# VCFA_bjt.net
KiCad netlist of a schematic drawn in EAGLE
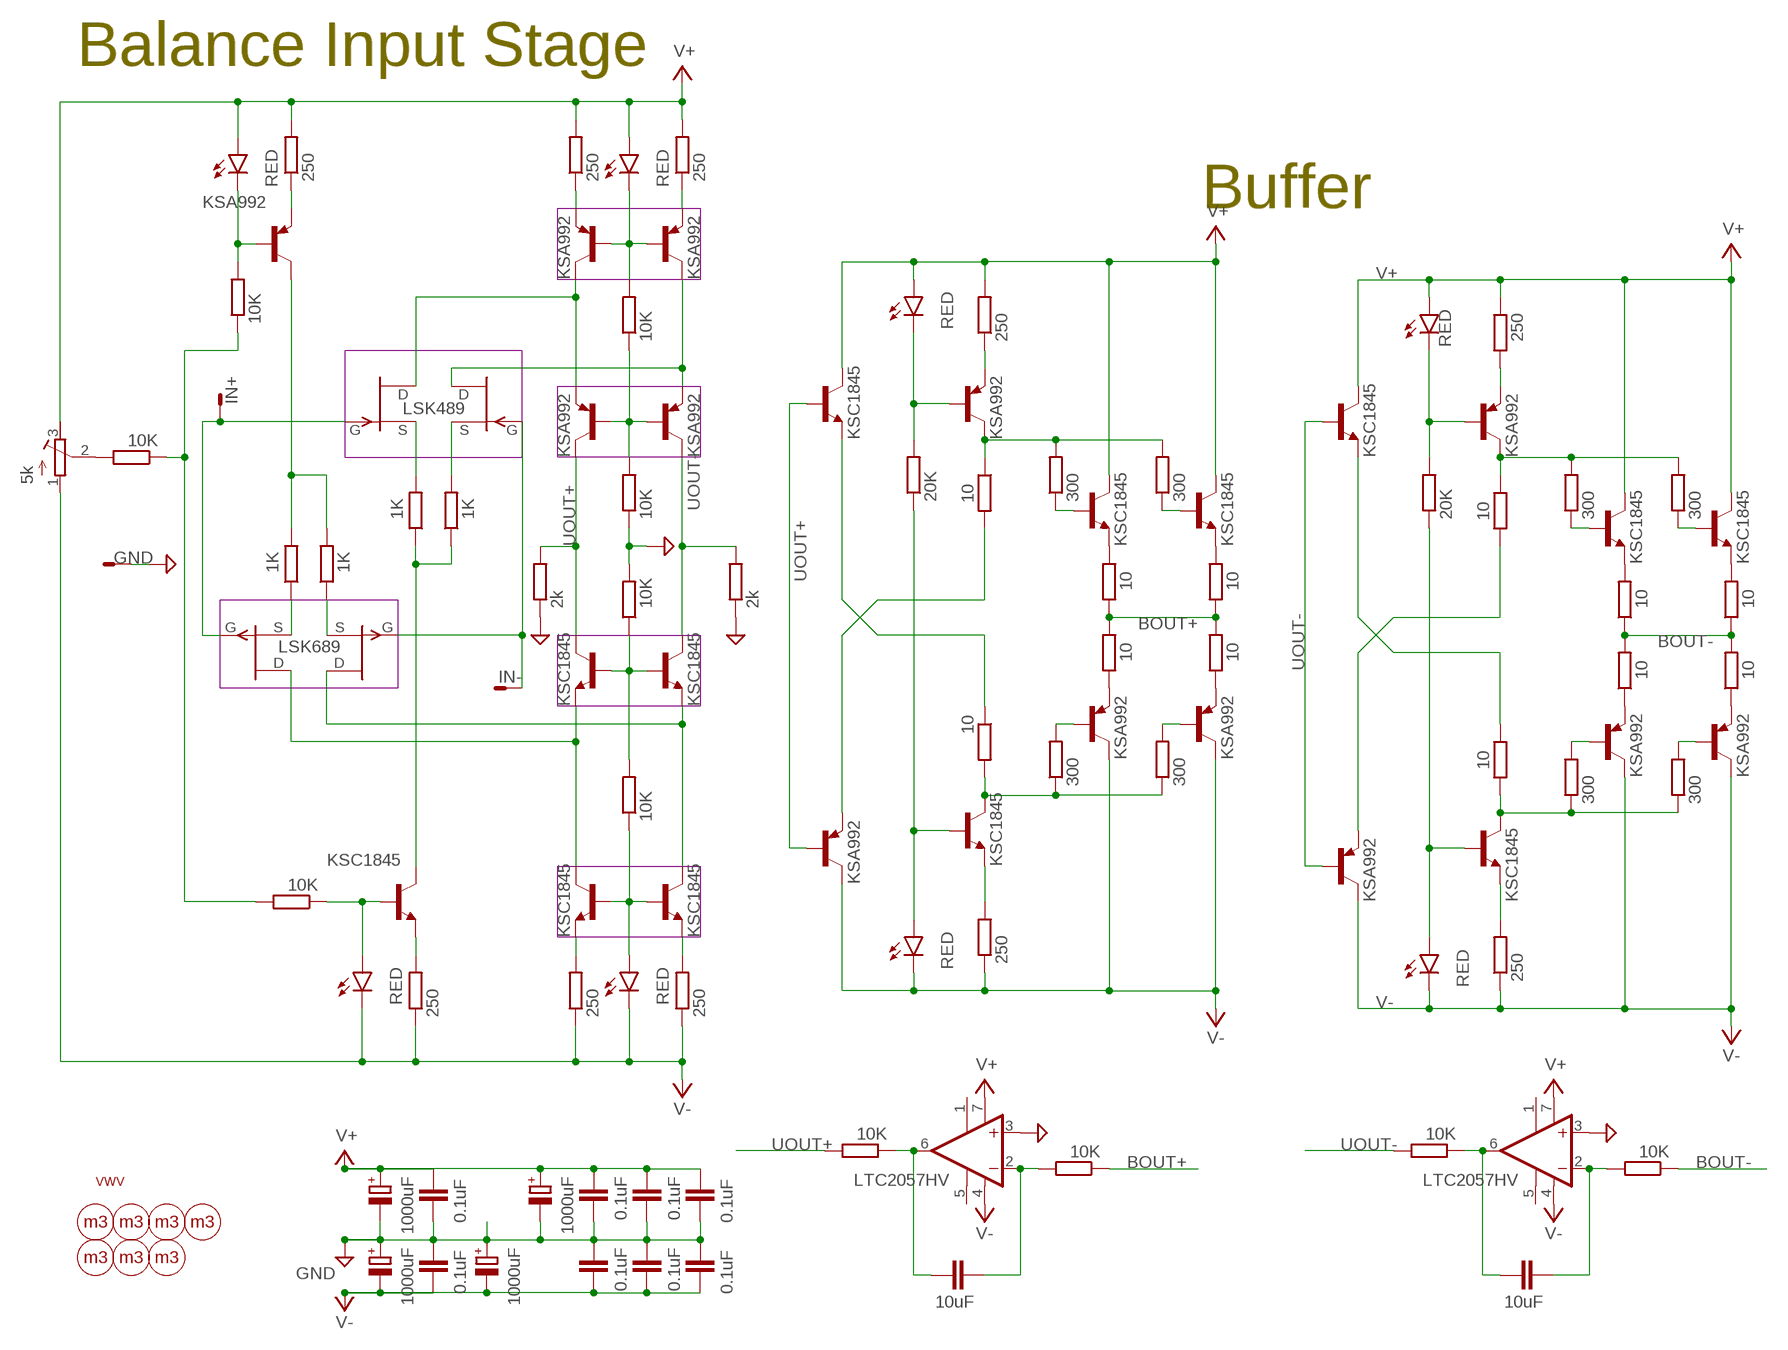
[diagram p0: schematic, sheet 1]
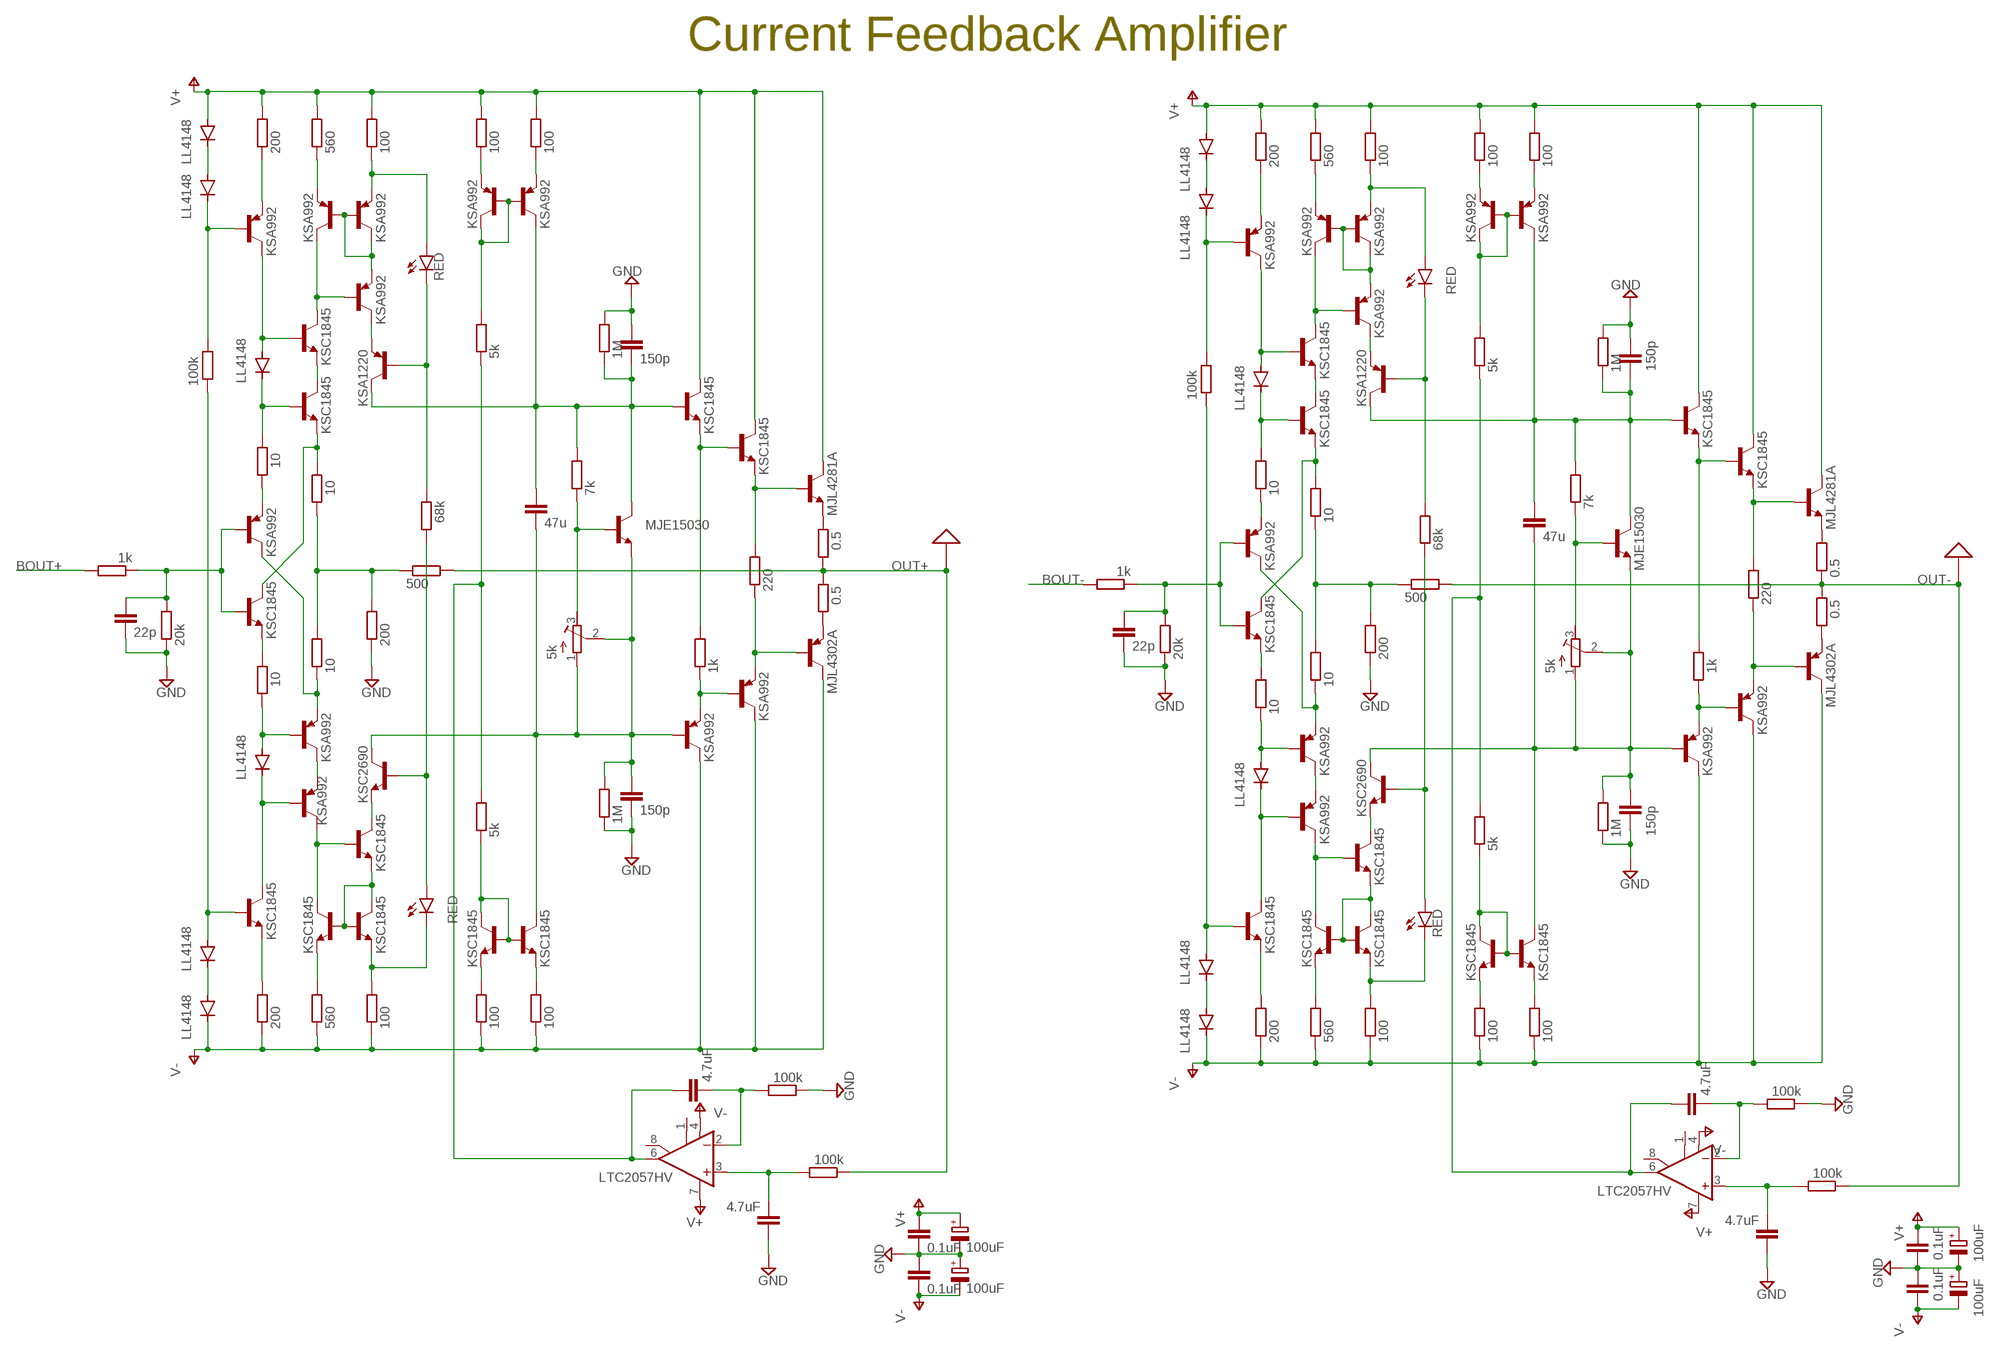
[diagram p1: schematic, sheet 2]
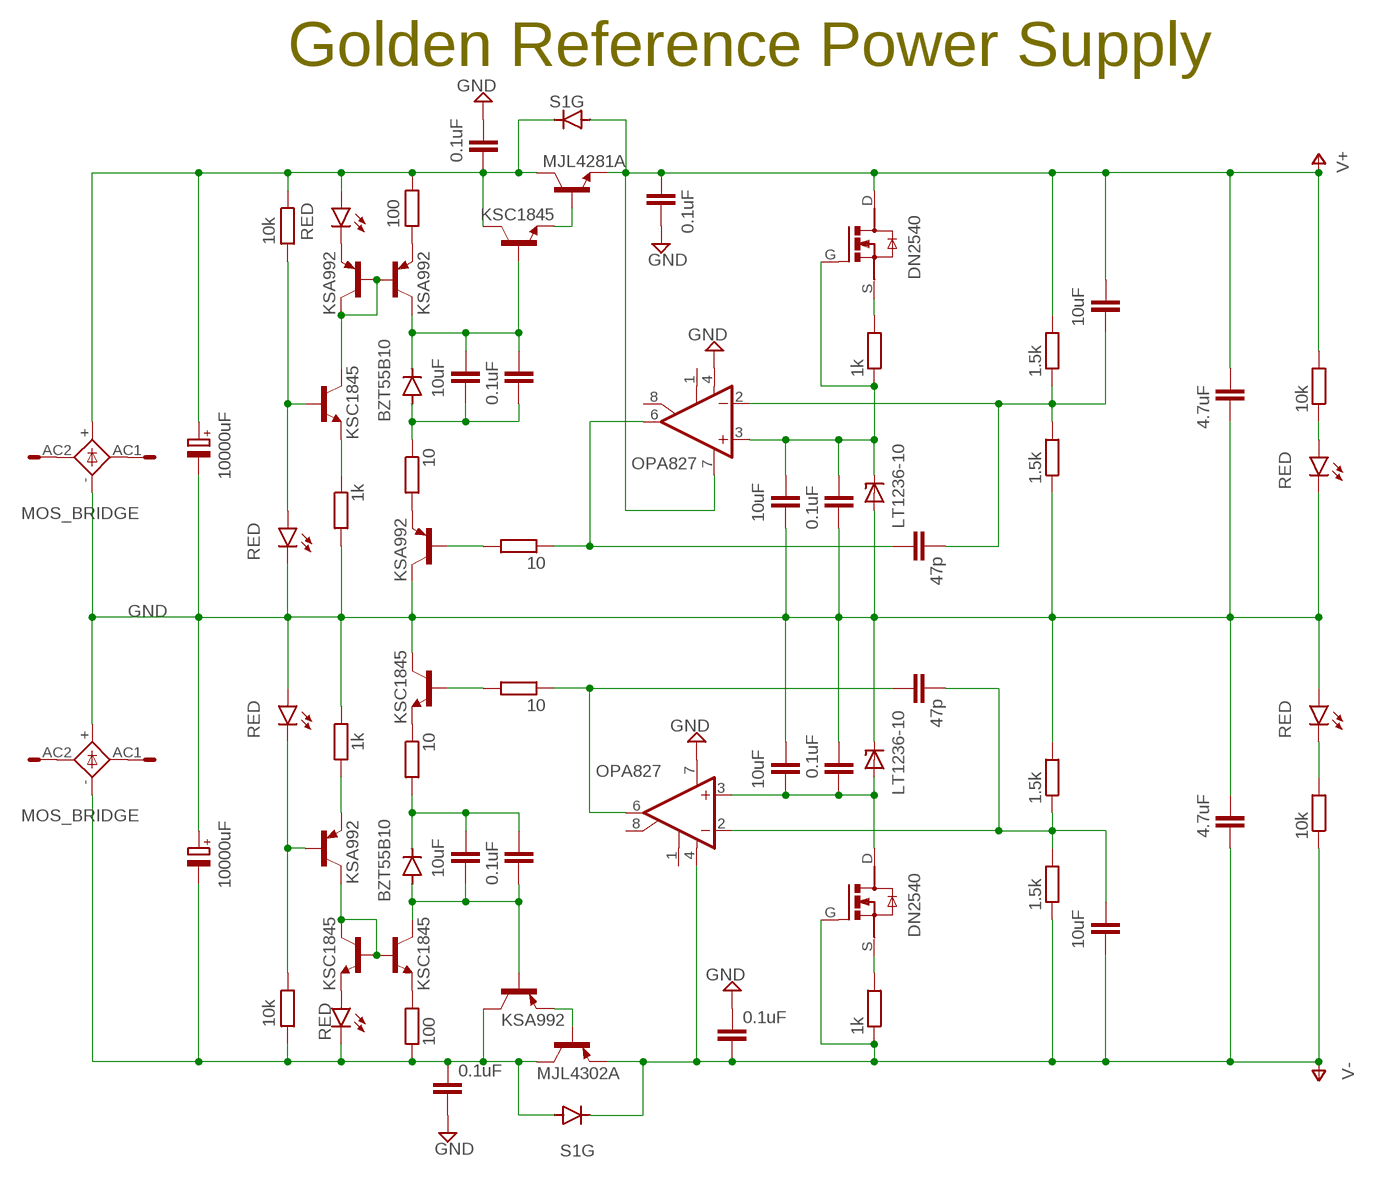
[diagram p2: schematic, sheet 3]

(export (version "E")
  (design (tool "Eeschema 10.0.6"))
  (components
    (comp (ref "C17")
      (value "22p")
      (footprint "eagle-import:C0805")
      (fields (field (name "SPICEPREFIX") "C"))
      (libsource (lib "eagle-import") (part "C-EUC0805"))
    )
    (comp (ref "C18")
      (value "47u")
      (footprint "eagle-import:C1210")
      (fields (field (name "SPICEPREFIX") "C"))
      (libsource (lib "eagle-import") (part "C-EUC1210"))
    )
    (comp (ref "C19")
      (value "150p")
      (footprint "eagle-import:C0805")
      (fields (field (name "SPICEPREFIX") "C"))
      (libsource (lib "eagle-import") (part "C-EUC0805"))
    )
    (comp (ref "C20")
      (value "150p")
      (footprint "eagle-import:C0805")
      (fields (field (name "SPICEPREFIX") "C"))
      (libsource (lib "eagle-import") (part "C-EUC0805"))
    )
    (comp (ref "C21")
      (value "4.7uF")
      (footprint "eagle-import:C1210")
      (fields (field (name "SPICEPREFIX") "C"))
      (libsource (lib "eagle-import") (part "C-EUC1210"))
    )
    (comp (ref "C22")
      (value "4.7uF")
      (footprint "eagle-import:C1210")
      (fields (field (name "SPICEPREFIX") "C"))
      (libsource (lib "eagle-import") (part "C-EUC1210"))
    )
    (comp (ref "C23")
      (value "0.1uF")
      (footprint "eagle-import:C0603K")
      (libsource (lib "eagle-import") (part "C-EUC0603K"))
    )
    (comp (ref "C24")
      (value "0.1uF")
      (footprint "eagle-import:C0603K")
      (libsource (lib "eagle-import") (part "C-EUC0603K"))
    )
    (comp (ref "C25")
      (value "100uF")
      (footprint "eagle-import:E3,5-8")
      (libsource (lib "eagle-import") (part "CPOL-EUE3.5-8"))
    )
    (comp (ref "C26")
      (value "100uF")
      (footprint "eagle-import:E3,5-8")
      (libsource (lib "eagle-import") (part "CPOL-EUE3.5-8"))
    )
    (comp (ref "C27")
      (value "22p")
      (footprint "eagle-import:C0805")
      (fields (field (name "SPICEPREFIX") "C"))
      (libsource (lib "eagle-import") (part "C-EUC0805"))
    )
    (comp (ref "C28")
      (value "47u")
      (footprint "eagle-import:C1210")
      (fields (field (name "SPICEPREFIX") "C"))
      (libsource (lib "eagle-import") (part "C-EUC1210"))
    )
    (comp (ref "C29")
      (value "150p")
      (footprint "eagle-import:C0805")
      (fields (field (name "SPICEPREFIX") "C"))
      (libsource (lib "eagle-import") (part "C-EUC0805"))
    )
    (comp (ref "C30")
      (value "150p")
      (footprint "eagle-import:C0805")
      (fields (field (name "SPICEPREFIX") "C"))
      (libsource (lib "eagle-import") (part "C-EUC0805"))
    )
    (comp (ref "C31")
      (value "4.7uF")
      (footprint "eagle-import:C1210")
      (fields (field (name "SPICEPREFIX") "C"))
      (libsource (lib "eagle-import") (part "C-EUC1210"))
    )
    (comp (ref "C32")
      (value "4.7uF")
      (footprint "eagle-import:C1210")
      (fields (field (name "SPICEPREFIX") "C"))
      (libsource (lib "eagle-import") (part "C-EUC1210"))
    )
    (comp (ref "C33")
      (value "0.1uF")
      (footprint "eagle-import:C0603K")
      (libsource (lib "eagle-import") (part "C-EUC0603K"))
    )
    (comp (ref "C34")
      (value "0.1uF")
      (footprint "eagle-import:C0603K")
      (libsource (lib "eagle-import") (part "C-EUC0603K"))
    )
    (comp (ref "C35")
      (value "100uF")
      (footprint "eagle-import:E3,5-8")
      (libsource (lib "eagle-import") (part "CPOL-EUE3.5-8"))
    )
    (comp (ref "C36")
      (value "100uF")
      (footprint "eagle-import:E3,5-8")
      (libsource (lib "eagle-import") (part "CPOL-EUE3.5-8"))
    )
    (comp (ref "D1")
      (value "LL4148")
      (footprint "eagle-import:SOD80C")
      (fields (field (name "SPICEPREFIX") "D"))
      (libsource (lib "eagle-import") (part "DIODE-SOD80C"))
    )
    (comp (ref "D2")
      (value "LL4148")
      (footprint "eagle-import:SOD80C")
      (fields (field (name "SPICEPREFIX") "D"))
      (libsource (lib "eagle-import") (part "DIODE-SOD80C"))
    )
    (comp (ref "D3")
      (value "LL4148")
      (footprint "eagle-import:SOD80C")
      (fields (field (name "SPICEPREFIX") "D"))
      (libsource (lib "eagle-import") (part "DIODE-SOD80C"))
    )
    (comp (ref "D4")
      (value "LL4148")
      (footprint "eagle-import:SOD80C")
      (fields (field (name "SPICEPREFIX") "D"))
      (libsource (lib "eagle-import") (part "DIODE-SOD80C"))
    )
    (comp (ref "D5")
      (value "LL4148")
      (footprint "eagle-import:SOD80C")
      (fields (field (name "SPICEPREFIX") "D"))
      (libsource (lib "eagle-import") (part "DIODE-SOD80C"))
    )
    (comp (ref "D6")
      (value "LL4148")
      (footprint "eagle-import:SOD80C")
      (fields (field (name "SPICEPREFIX") "D"))
      (libsource (lib "eagle-import") (part "DIODE-SOD80C"))
    )
    (comp (ref "D7")
      (value "LL4148")
      (footprint "eagle-import:SOD80C")
      (fields (field (name "SPICEPREFIX") "D"))
      (libsource (lib "eagle-import") (part "DIODE-SOD80C"))
    )
    (comp (ref "D8")
      (value "LL4148")
      (footprint "eagle-import:SOD80C")
      (fields (field (name "SPICEPREFIX") "D"))
      (libsource (lib "eagle-import") (part "DIODE-SOD80C"))
    )
    (comp (ref "D9")
      (value "LL4148")
      (footprint "eagle-import:SOD80C")
      (fields (field (name "SPICEPREFIX") "D"))
      (libsource (lib "eagle-import") (part "DIODE-SOD80C"))
    )
    (comp (ref "D10")
      (value "LL4148")
      (footprint "eagle-import:SOD80C")
      (fields (field (name "SPICEPREFIX") "D"))
      (libsource (lib "eagle-import") (part "DIODE-SOD80C"))
    )
    (comp (ref "D11")
      (value "LL4148")
      (footprint "eagle-import:SOD80C")
      (fields (field (name "SPICEPREFIX") "D"))
      (libsource (lib "eagle-import") (part "DIODE-SOD80C"))
    )
    (comp (ref "D12")
      (value "LL4148")
      (footprint "eagle-import:SOD80C")
      (fields (field (name "SPICEPREFIX") "D"))
      (libsource (lib "eagle-import") (part "DIODE-SOD80C"))
    )
    (comp (ref "IC3")
      (value "LTC2057HV")
      (footprint "eagle-import:SOIC8")
      (libsource (lib "eagle-import") (part "LT10S837I"))
    )
    (comp (ref "IC4")
      (value "LTC2057HV")
      (footprint "eagle-import:SOIC8")
      (libsource (lib "eagle-import") (part "LT10S837I"))
    )
    (comp (ref "LED9")
      (value "RED")
      (footprint "eagle-import:LED_SML1206")
      (fields (field (name "SPICEPREFIX") "D"))
      (libsource (lib "eagle-import") (part "LEDVWV1206"))
    )
    (comp (ref "LED10")
      (value "RED")
      (footprint "eagle-import:LED_SML1206")
      (fields (field (name "SPICEPREFIX") "D"))
      (libsource (lib "eagle-import") (part "LEDVWV1206"))
    )
    (comp (ref "LED11")
      (value "RED")
      (footprint "eagle-import:LED_SML1206")
      (fields (field (name "SPICEPREFIX") "D"))
      (libsource (lib "eagle-import") (part "LEDVWV1206"))
    )
    (comp (ref "LED12")
      (value "RED")
      (footprint "eagle-import:LED_SML1206")
      (fields (field (name "SPICEPREFIX") "D"))
      (libsource (lib "eagle-import") (part "LEDVWV1206"))
    )
    (comp (ref "PAD1")
      (value "PAD")
      (footprint "eagle-import:PAD-16")
      (libsource (lib "eagle-import") (part "PAD"))
    )
    (comp (ref "PAD2")
      (value "PAD")
      (footprint "eagle-import:PAD-16")
      (libsource (lib "eagle-import") (part "PAD"))
    )
    (comp (ref "Q25")
      (value "KSA992")
      (footprint "eagle-import:TRANSISTOR_TO92-ECB_P")
      (fields (field (name "SPICEPREFIX") "Q"))
      (libsource (lib "eagle-import") (part "BJT_PNPKSA992"))
    )
    (comp (ref "Q26")
      (value "KSA992")
      (footprint "eagle-import:TRANSISTOR_TO92-ECB_P")
      (fields (field (name "SPICEPREFIX") "Q"))
      (libsource (lib "eagle-import") (part "BJT_PNPKSA992"))
    )
    (comp (ref "Q27")
      (value "KSC1845")
      (footprint "eagle-import:TRANSISTOR_TO92-ECB_N")
      (fields (field (name "SPICEPREFIX") "Q"))
      (libsource (lib "eagle-import") (part "BJT_NPNKSC1845"))
    )
    (comp (ref "Q28")
      (value "KSC1845")
      (footprint "eagle-import:TRANSISTOR_TO92-ECB_N")
      (fields (field (name "SPICEPREFIX") "Q"))
      (libsource (lib "eagle-import") (part "BJT_NPNKSC1845"))
    )
    (comp (ref "Q29")
      (value "KSC1845")
      (footprint "eagle-import:TRANSISTOR_TO92-ECB_N")
      (fields (field (name "SPICEPREFIX") "Q"))
      (libsource (lib "eagle-import") (part "BJT_NPNKSC1845"))
    )
    (comp (ref "Q30")
      (value "KSC1845")
      (footprint "eagle-import:TRANSISTOR_TO92-ECB_N")
      (fields (field (name "SPICEPREFIX") "Q"))
      (libsource (lib "eagle-import") (part "BJT_NPNKSC1845"))
    )
    (comp (ref "Q31")
      (value "KSA992")
      (footprint "eagle-import:TRANSISTOR_TO92-ECB_P")
      (fields (field (name "SPICEPREFIX") "Q"))
      (libsource (lib "eagle-import") (part "BJT_PNPKSA992"))
    )
    (comp (ref "Q32")
      (value "KSA992")
      (footprint "eagle-import:TRANSISTOR_TO92-ECB_P")
      (fields (field (name "SPICEPREFIX") "Q"))
      (libsource (lib "eagle-import") (part "BJT_PNPKSA992"))
    )
    (comp (ref "Q33")
      (value "KSA992")
      (footprint "eagle-import:TRANSISTOR_TO92-ECB_P")
      (fields (field (name "SPICEPREFIX") "Q"))
      (libsource (lib "eagle-import") (part "BJT_PNPKSA992"))
    )
    (comp (ref "Q34")
      (value "KSC1845")
      (footprint "eagle-import:TRANSISTOR_TO92-ECB_N")
      (fields (field (name "SPICEPREFIX") "Q"))
      (libsource (lib "eagle-import") (part "BJT_NPNKSC1845"))
    )
    (comp (ref "Q35")
      (value "KSA992")
      (footprint "eagle-import:TRANSISTOR_TO92-ECB_P")
      (fields (field (name "SPICEPREFIX") "Q"))
      (libsource (lib "eagle-import") (part "BJT_PNPKSA992"))
    )
    (comp (ref "Q36")
      (value "KSA992")
      (footprint "eagle-import:TRANSISTOR_TO92-ECB_P")
      (fields (field (name "SPICEPREFIX") "Q"))
      (libsource (lib "eagle-import") (part "BJT_PNPKSA992"))
    )
    (comp (ref "Q37")
      (value "KSC1845")
      (footprint "eagle-import:TRANSISTOR_TO92-ECB_N")
      (fields (field (name "SPICEPREFIX") "Q"))
      (libsource (lib "eagle-import") (part "BJT_NPNKSC1845"))
    )
    (comp (ref "Q38")
      (value "KSC1845")
      (footprint "eagle-import:TRANSISTOR_TO92-ECB_N")
      (fields (field (name "SPICEPREFIX") "Q"))
      (libsource (lib "eagle-import") (part "BJT_NPNKSC1845"))
    )
    (comp (ref "Q39")
      (value "KSA1220")
      (footprint "eagle-import:TRANSISTOR_TO126_P")
      (fields (field (name "SPICEPREFIX") "Q"))
      (libsource (lib "eagle-import") (part "BJT_PNPKSA1220"))
    )
    (comp (ref "Q40")
      (value "KSC2690")
      (footprint "eagle-import:TRANSISTOR_TO126_N")
      (fields (field (name "SPICEPREFIX") "Q"))
      (libsource (lib "eagle-import") (part "BJT_NPNKSC2690"))
    )
    (comp (ref "Q41")
      (value "KSA992")
      (footprint "eagle-import:TRANSISTOR_TO92-ECB_P")
      (fields (field (name "SPICEPREFIX") "Q"))
      (libsource (lib "eagle-import") (part "BJT_PNPKSA992"))
    )
    (comp (ref "Q42")
      (value "KSC1845")
      (footprint "eagle-import:TRANSISTOR_TO92-ECB_N")
      (fields (field (name "SPICEPREFIX") "Q"))
      (libsource (lib "eagle-import") (part "BJT_NPNKSC1845"))
    )
    (comp (ref "Q43")
      (value "KSA992")
      (footprint "eagle-import:TRANSISTOR_TO92-ECB_P")
      (fields (field (name "SPICEPREFIX") "Q"))
      (libsource (lib "eagle-import") (part "BJT_PNPKSA992"))
    )
    (comp (ref "Q44")
      (value "KSC1845")
      (footprint "eagle-import:TRANSISTOR_TO92-ECB_N")
      (fields (field (name "SPICEPREFIX") "Q"))
      (libsource (lib "eagle-import") (part "BJT_NPNKSC1845"))
    )
    (comp (ref "Q45")
      (value "MJE15030")
      (footprint "eagle-import:TRANSISTOR_TO220_BCE_N")
      (fields (field (name "SPICEPREFIX") "Q"))
      (libsource (lib "eagle-import") (part "BJT_NPNMJE15030"))
    )
    (comp (ref "Q46")
      (value "KSC1845")
      (footprint "eagle-import:TRANSISTOR_TO92-ECB_N")
      (fields (field (name "SPICEPREFIX") "Q"))
      (libsource (lib "eagle-import") (part "BJT_NPNKSC1845"))
    )
    (comp (ref "Q47")
      (value "KSA992")
      (footprint "eagle-import:TRANSISTOR_TO92-ECB_P")
      (fields (field (name "SPICEPREFIX") "Q"))
      (libsource (lib "eagle-import") (part "BJT_PNPKSA992"))
    )
    (comp (ref "Q48")
      (value "KSC1845")
      (footprint "eagle-import:TRANSISTOR_TO92-ECB_N")
      (fields (field (name "SPICEPREFIX") "Q"))
      (libsource (lib "eagle-import") (part "BJT_NPNKSC1845"))
    )
    (comp (ref "Q49")
      (value "KSA992")
      (footprint "eagle-import:TRANSISTOR_TO92-ECB_P")
      (fields (field (name "SPICEPREFIX") "Q"))
      (libsource (lib "eagle-import") (part "BJT_PNPKSA992"))
    )
    (comp (ref "Q50")
      (value "MJL4281A")
      (footprint "eagle-import:TRANSISTOR_TO247_BCE_N")
      (fields (field (name "SPICEPREFIX") "Q"))
      (libsource (lib "eagle-import") (part "BJT_NPNMJL4281"))
    )
    (comp (ref "Q51")
      (value "MJL4302A")
      (footprint "eagle-import:TRANSISTOR_TO247_BCE_P")
      (fields (field (name "SPICEPREFIX") "Q"))
      (libsource (lib "eagle-import") (part "BJT_PNPMJL4302"))
    )
    (comp (ref "Q52")
      (value "KSA992")
      (footprint "eagle-import:TRANSISTOR_TO92-ECB_P")
      (fields (field (name "SPICEPREFIX") "Q"))
      (libsource (lib "eagle-import") (part "BJT_PNPKSA992"))
    )
    (comp (ref "Q53")
      (value "KSA992")
      (footprint "eagle-import:TRANSISTOR_TO92-ECB_P")
      (fields (field (name "SPICEPREFIX") "Q"))
      (libsource (lib "eagle-import") (part "BJT_PNPKSA992"))
    )
    (comp (ref "Q54")
      (value "KSC1845")
      (footprint "eagle-import:TRANSISTOR_TO92-ECB_N")
      (fields (field (name "SPICEPREFIX") "Q"))
      (libsource (lib "eagle-import") (part "BJT_NPNKSC1845"))
    )
    (comp (ref "Q55")
      (value "KSC1845")
      (footprint "eagle-import:TRANSISTOR_TO92-ECB_N")
      (fields (field (name "SPICEPREFIX") "Q"))
      (libsource (lib "eagle-import") (part "BJT_NPNKSC1845"))
    )
    (comp (ref "Q56")
      (value "KSC1845")
      (footprint "eagle-import:TRANSISTOR_TO92-ECB_N")
      (fields (field (name "SPICEPREFIX") "Q"))
      (libsource (lib "eagle-import") (part "BJT_NPNKSC1845"))
    )
    (comp (ref "Q57")
      (value "KSC1845")
      (footprint "eagle-import:TRANSISTOR_TO92-ECB_N")
      (fields (field (name "SPICEPREFIX") "Q"))
      (libsource (lib "eagle-import") (part "BJT_NPNKSC1845"))
    )
    (comp (ref "Q58")
      (value "KSA992")
      (footprint "eagle-import:TRANSISTOR_TO92-ECB_P")
      (fields (field (name "SPICEPREFIX") "Q"))
      (libsource (lib "eagle-import") (part "BJT_PNPKSA992"))
    )
    (comp (ref "Q59")
      (value "KSA992")
      (footprint "eagle-import:TRANSISTOR_TO92-ECB_P")
      (fields (field (name "SPICEPREFIX") "Q"))
      (libsource (lib "eagle-import") (part "BJT_PNPKSA992"))
    )
    (comp (ref "Q60")
      (value "KSA992")
      (footprint "eagle-import:TRANSISTOR_TO92-ECB_P")
      (fields (field (name "SPICEPREFIX") "Q"))
      (libsource (lib "eagle-import") (part "BJT_PNPKSA992"))
    )
    (comp (ref "Q61")
      (value "KSC1845")
      (footprint "eagle-import:TRANSISTOR_TO92-ECB_N")
      (fields (field (name "SPICEPREFIX") "Q"))
      (libsource (lib "eagle-import") (part "BJT_NPNKSC1845"))
    )
    (comp (ref "Q62")
      (value "KSA992")
      (footprint "eagle-import:TRANSISTOR_TO92-ECB_P")
      (fields (field (name "SPICEPREFIX") "Q"))
      (libsource (lib "eagle-import") (part "BJT_PNPKSA992"))
    )
    (comp (ref "Q63")
      (value "KSA992")
      (footprint "eagle-import:TRANSISTOR_TO92-ECB_P")
      (fields (field (name "SPICEPREFIX") "Q"))
      (libsource (lib "eagle-import") (part "BJT_PNPKSA992"))
    )
    (comp (ref "Q64")
      (value "KSC1845")
      (footprint "eagle-import:TRANSISTOR_TO92-ECB_N")
      (fields (field (name "SPICEPREFIX") "Q"))
      (libsource (lib "eagle-import") (part "BJT_NPNKSC1845"))
    )
    (comp (ref "Q65")
      (value "KSC1845")
      (footprint "eagle-import:TRANSISTOR_TO92-ECB_N")
      (fields (field (name "SPICEPREFIX") "Q"))
      (libsource (lib "eagle-import") (part "BJT_NPNKSC1845"))
    )
    (comp (ref "Q66")
      (value "KSA1220")
      (footprint "eagle-import:TRANSISTOR_TO126_P")
      (fields (field (name "SPICEPREFIX") "Q"))
      (libsource (lib "eagle-import") (part "BJT_PNPKSA1220"))
    )
    (comp (ref "Q67")
      (value "KSC2690")
      (footprint "eagle-import:TRANSISTOR_TO126_N")
      (fields (field (name "SPICEPREFIX") "Q"))
      (libsource (lib "eagle-import") (part "BJT_NPNKSC2690"))
    )
    (comp (ref "Q68")
      (value "KSA992")
      (footprint "eagle-import:TRANSISTOR_TO92-ECB_P")
      (fields (field (name "SPICEPREFIX") "Q"))
      (libsource (lib "eagle-import") (part "BJT_PNPKSA992"))
    )
    (comp (ref "Q69")
      (value "KSC1845")
      (footprint "eagle-import:TRANSISTOR_TO92-ECB_N")
      (fields (field (name "SPICEPREFIX") "Q"))
      (libsource (lib "eagle-import") (part "BJT_NPNKSC1845"))
    )
    (comp (ref "Q70")
      (value "KSA992")
      (footprint "eagle-import:TRANSISTOR_TO92-ECB_P")
      (fields (field (name "SPICEPREFIX") "Q"))
      (libsource (lib "eagle-import") (part "BJT_PNPKSA992"))
    )
    (comp (ref "Q71")
      (value "KSC1845")
      (footprint "eagle-import:TRANSISTOR_TO92-ECB_N")
      (fields (field (name "SPICEPREFIX") "Q"))
      (libsource (lib "eagle-import") (part "BJT_NPNKSC1845"))
    )
    (comp (ref "Q72")
      (value "MJE15030")
      (footprint "eagle-import:TRANSISTOR_TO220_BCE_N")
      (fields (field (name "SPICEPREFIX") "Q"))
      (libsource (lib "eagle-import") (part "BJT_NPNMJE15030"))
    )
    (comp (ref "Q73")
      (value "KSC1845")
      (footprint "eagle-import:TRANSISTOR_TO92-ECB_N")
      (fields (field (name "SPICEPREFIX") "Q"))
      (libsource (lib "eagle-import") (part "BJT_NPNKSC1845"))
    )
    (comp (ref "Q74")
      (value "KSA992")
      (footprint "eagle-import:TRANSISTOR_TO92-ECB_P")
      (fields (field (name "SPICEPREFIX") "Q"))
      (libsource (lib "eagle-import") (part "BJT_PNPKSA992"))
    )
    (comp (ref "Q75")
      (value "KSC1845")
      (footprint "eagle-import:TRANSISTOR_TO92-ECB_N")
      (fields (field (name "SPICEPREFIX") "Q"))
      (libsource (lib "eagle-import") (part "BJT_NPNKSC1845"))
    )
    (comp (ref "Q76")
      (value "KSA992")
      (footprint "eagle-import:TRANSISTOR_TO92-ECB_P")
      (fields (field (name "SPICEPREFIX") "Q"))
      (libsource (lib "eagle-import") (part "BJT_PNPKSA992"))
    )
    (comp (ref "Q77")
      (value "MJL4281A")
      (footprint "eagle-import:TRANSISTOR_TO247_BCE_N")
      (fields (field (name "SPICEPREFIX") "Q"))
      (libsource (lib "eagle-import") (part "BJT_NPNMJL4281"))
    )
    (comp (ref "Q78")
      (value "MJL4302A")
      (footprint "eagle-import:TRANSISTOR_TO247_BCE_P")
      (fields (field (name "SPICEPREFIX") "Q"))
      (libsource (lib "eagle-import") (part "BJT_PNPMJL4302"))
    )
    (comp (ref "R51")
      (value "1k")
      (footprint "eagle-import:MINI_MELF-0204W")
      (fields (field (name "SPICEPREFIX") "R"))
      (libsource (lib "eagle-import") (part "R-EU_MELF0204W"))
    )
    (comp (ref "R52")
      (value "20k")
      (footprint "eagle-import:MINI_MELF-0204W")
      (fields (field (name "SPICEPREFIX") "R"))
      (libsource (lib "eagle-import") (part "R-EU_MELF0204W"))
    )
    (comp (ref "R53")
      (value "100k")
      (footprint "eagle-import:MINI_MELF-0204W")
      (fields (field (name "SPICEPREFIX") "R"))
      (libsource (lib "eagle-import") (part "R-EU_MELF0204W"))
    )
    (comp (ref "R54")
      (value "200")
      (footprint "eagle-import:MINI_MELF-0204W")
      (fields (field (name "SPICEPREFIX") "R"))
      (libsource (lib "eagle-import") (part "R-EU_MELF0204W"))
    )
    (comp (ref "R55")
      (value "10")
      (footprint "eagle-import:MINI_MELF-0204W")
      (fields (field (name "SPICEPREFIX") "R"))
      (libsource (lib "eagle-import") (part "R-EU_MELF0204W"))
    )
    (comp (ref "R56")
      (value "10")
      (footprint "eagle-import:MINI_MELF-0204W")
      (fields (field (name "SPICEPREFIX") "R"))
      (libsource (lib "eagle-import") (part "R-EU_MELF0204W"))
    )
    (comp (ref "R57")
      (value "200")
      (footprint "eagle-import:MINI_MELF-0204W")
      (fields (field (name "SPICEPREFIX") "R"))
      (libsource (lib "eagle-import") (part "R-EU_MELF0204W"))
    )
    (comp (ref "R58")
      (value "560")
      (footprint "eagle-import:MINI_MELF-0204W")
      (fields (field (name "SPICEPREFIX") "R"))
      (libsource (lib "eagle-import") (part "R-EU_MELF0204W"))
    )
    (comp (ref "R59")
      (value "10")
      (footprint "eagle-import:MINI_MELF-0204W")
      (fields (field (name "SPICEPREFIX") "R"))
      (libsource (lib "eagle-import") (part "R-EU_MELF0204W"))
    )
    (comp (ref "R60")
      (value "10")
      (footprint "eagle-import:MINI_MELF-0204W")
      (fields (field (name "SPICEPREFIX") "R"))
      (libsource (lib "eagle-import") (part "R-EU_MELF0204W"))
    )
    (comp (ref "R61")
      (value "560")
      (footprint "eagle-import:MINI_MELF-0204W")
      (fields (field (name "SPICEPREFIX") "R"))
      (libsource (lib "eagle-import") (part "R-EU_MELF0204W"))
    )
    (comp (ref "R62")
      (value "100")
      (footprint "eagle-import:MINI_MELF-0204W")
      (fields (field (name "SPICEPREFIX") "R"))
      (libsource (lib "eagle-import") (part "R-EU_MELF0204W"))
    )
    (comp (ref "R63")
      (value "200")
      (footprint "eagle-import:MINI_MELF-0204W")
      (fields (field (name "SPICEPREFIX") "R"))
      (libsource (lib "eagle-import") (part "R-EU_MELF0204W"))
    )
    (comp (ref "R64")
      (value "100")
      (footprint "eagle-import:MINI_MELF-0204W")
      (fields (field (name "SPICEPREFIX") "R"))
      (libsource (lib "eagle-import") (part "R-EU_MELF0204W"))
    )
    (comp (ref "R65")
      (value "68k")
      (footprint "eagle-import:MINI_MELF-0204W")
      (fields (field (name "SPICEPREFIX") "R"))
      (libsource (lib "eagle-import") (part "R-EU_MELF0204W"))
    )
    (comp (ref "R66")
      (value "500")
      (footprint "eagle-import:MINI_MELF-0204W")
      (fields (field (name "SPICEPREFIX") "R"))
      (libsource (lib "eagle-import") (part "R-EU_MELF0204W"))
    )
    (comp (ref "R67")
      (value "100")
      (footprint "eagle-import:MINI_MELF-0204W")
      (fields (field (name "SPICEPREFIX") "R"))
      (libsource (lib "eagle-import") (part "R-EU_MELF0204W"))
    )
    (comp (ref "R68")
      (value "5k")
      (footprint "eagle-import:MINI_MELF-0204W")
      (fields (field (name "SPICEPREFIX") "R"))
      (libsource (lib "eagle-import") (part "R-EU_MELF0204W"))
    )
    (comp (ref "R69")
      (value "5k")
      (footprint "eagle-import:MINI_MELF-0204W")
      (fields (field (name "SPICEPREFIX") "R"))
      (libsource (lib "eagle-import") (part "R-EU_MELF0204W"))
    )
    (comp (ref "R70")
      (value "100")
      (footprint "eagle-import:MINI_MELF-0204W")
      (fields (field (name "SPICEPREFIX") "R"))
      (libsource (lib "eagle-import") (part "R-EU_MELF0204W"))
    )
    (comp (ref "R71")
      (value "100")
      (footprint "eagle-import:MINI_MELF-0204W")
      (fields (field (name "SPICEPREFIX") "R"))
      (libsource (lib "eagle-import") (part "R-EU_MELF0204W"))
    )
    (comp (ref "R72")
      (value "100")
      (footprint "eagle-import:MINI_MELF-0204W")
      (fields (field (name "SPICEPREFIX") "R"))
      (libsource (lib "eagle-import") (part "R-EU_MELF0204W"))
    )
    (comp (ref "R73")
      (value "7k")
      (footprint "eagle-import:MINI_MELF-0204W")
      (fields (field (name "SPICEPREFIX") "R"))
      (libsource (lib "eagle-import") (part "R-EU_MELF0204W"))
    )
    (comp (ref "R74")
      (value "5k")
      (footprint "eagle-import:RTRIM3296W")
      (fields (field (name "SPICEPREFIX") "Z"))
      (libsource (lib "eagle-import") (part "R-TRIMM3296W"))
    )
    (comp (ref "R75")
      (value "1M")
      (footprint "eagle-import:MINI_MELF-0204W")
      (fields (field (name "SPICEPREFIX") "R"))
      (libsource (lib "eagle-import") (part "R-EU_MELF0204W"))
    )
    (comp (ref "R76")
      (value "1M")
      (footprint "eagle-import:MINI_MELF-0204W")
      (fields (field (name "SPICEPREFIX") "R"))
      (libsource (lib "eagle-import") (part "R-EU_MELF0204W"))
    )
    (comp (ref "R77")
      (value "1k")
      (footprint "eagle-import:MINI_MELF-0204W")
      (fields (field (name "SPICEPREFIX") "R"))
      (libsource (lib "eagle-import") (part "R-EU_MELF0204W"))
    )
    (comp (ref "R78")
      (value "220")
      (footprint "eagle-import:MINI_MELF-0204W")
      (fields (field (name "SPICEPREFIX") "R"))
      (libsource (lib "eagle-import") (part "R-EU_MELF0204W"))
    )
    (comp (ref "R79")
      (value "100k")
      (footprint "eagle-import:MINI_MELF-0204W")
      (fields (field (name "SPICEPREFIX") "R"))
      (libsource (lib "eagle-import") (part "R-EU_MELF0204W"))
    )
    (comp (ref "R80")
      (value "0.5")
      (footprint "eagle-import:R2512")
      (fields (field (name "SPICEPREFIX") "R"))
      (libsource (lib "eagle-import") (part "R-EU_R2512"))
    )
    (comp (ref "R81")
      (value "0.5")
      (footprint "eagle-import:R2512")
      (fields (field (name "SPICEPREFIX") "R"))
      (libsource (lib "eagle-import") (part "R-EU_R2512"))
    )
    (comp (ref "R82")
      (value "100k")
      (footprint "eagle-import:MINI_MELF-0204W")
      (fields (field (name "SPICEPREFIX") "R"))
      (libsource (lib "eagle-import") (part "R-EU_MELF0204W"))
    )
    (comp (ref "R83")
      (value "1k")
      (footprint "eagle-import:MINI_MELF-0204W")
      (fields (field (name "SPICEPREFIX") "R"))
      (libsource (lib "eagle-import") (part "R-EU_MELF0204W"))
    )
    (comp (ref "R84")
      (value "20k")
      (footprint "eagle-import:MINI_MELF-0204W")
      (fields (field (name "SPICEPREFIX") "R"))
      (libsource (lib "eagle-import") (part "R-EU_MELF0204W"))
    )
    (comp (ref "R85")
      (value "100k")
      (footprint "eagle-import:MINI_MELF-0204W")
      (fields (field (name "SPICEPREFIX") "R"))
      (libsource (lib "eagle-import") (part "R-EU_MELF0204W"))
    )
    (comp (ref "R86")
      (value "200")
      (footprint "eagle-import:MINI_MELF-0204W")
      (fields (field (name "SPICEPREFIX") "R"))
      (libsource (lib "eagle-import") (part "R-EU_MELF0204W"))
    )
    (comp (ref "R87")
      (value "10")
      (footprint "eagle-import:MINI_MELF-0204W")
      (fields (field (name "SPICEPREFIX") "R"))
      (libsource (lib "eagle-import") (part "R-EU_MELF0204W"))
    )
    (comp (ref "R88")
      (value "10")
      (footprint "eagle-import:MINI_MELF-0204W")
      (fields (field (name "SPICEPREFIX") "R"))
      (libsource (lib "eagle-import") (part "R-EU_MELF0204W"))
    )
    (comp (ref "R89")
      (value "200")
      (footprint "eagle-import:MINI_MELF-0204W")
      (fields (field (name "SPICEPREFIX") "R"))
      (libsource (lib "eagle-import") (part "R-EU_MELF0204W"))
    )
    (comp (ref "R90")
      (value "560")
      (footprint "eagle-import:MINI_MELF-0204W")
      (fields (field (name "SPICEPREFIX") "R"))
      (libsource (lib "eagle-import") (part "R-EU_MELF0204W"))
    )
    (comp (ref "R91")
      (value "10")
      (footprint "eagle-import:MINI_MELF-0204W")
      (fields (field (name "SPICEPREFIX") "R"))
      (libsource (lib "eagle-import") (part "R-EU_MELF0204W"))
    )
    (comp (ref "R92")
      (value "10")
      (footprint "eagle-import:MINI_MELF-0204W")
      (fields (field (name "SPICEPREFIX") "R"))
      (libsource (lib "eagle-import") (part "R-EU_MELF0204W"))
    )
    (comp (ref "R93")
      (value "560")
      (footprint "eagle-import:MINI_MELF-0204W")
      (fields (field (name "SPICEPREFIX") "R"))
      (libsource (lib "eagle-import") (part "R-EU_MELF0204W"))
    )
    (comp (ref "R94")
      (value "100")
      (footprint "eagle-import:MINI_MELF-0204W")
      (fields (field (name "SPICEPREFIX") "R"))
      (libsource (lib "eagle-import") (part "R-EU_MELF0204W"))
    )
    (comp (ref "R95")
      (value "200")
      (footprint "eagle-import:MINI_MELF-0204W")
      (fields (field (name "SPICEPREFIX") "R"))
      (libsource (lib "eagle-import") (part "R-EU_MELF0204W"))
    )
    (comp (ref "R96")
      (value "100")
      (footprint "eagle-import:MINI_MELF-0204W")
      (fields (field (name "SPICEPREFIX") "R"))
      (libsource (lib "eagle-import") (part "R-EU_MELF0204W"))
    )
    (comp (ref "R97")
      (value "68k")
      (footprint "eagle-import:MINI_MELF-0204W")
      (fields (field (name "SPICEPREFIX") "R"))
      (libsource (lib "eagle-import") (part "R-EU_MELF0204W"))
    )
    (comp (ref "R98")
      (value "500")
      (footprint "eagle-import:MINI_MELF-0204W")
      (fields (field (name "SPICEPREFIX") "R"))
      (libsource (lib "eagle-import") (part "R-EU_MELF0204W"))
    )
    (comp (ref "R99")
      (value "100")
      (footprint "eagle-import:MINI_MELF-0204W")
      (fields (field (name "SPICEPREFIX") "R"))
      (libsource (lib "eagle-import") (part "R-EU_MELF0204W"))
    )
    (comp (ref "R100")
      (value "5k")
      (footprint "eagle-import:MINI_MELF-0204W")
      (fields (field (name "SPICEPREFIX") "R"))
      (libsource (lib "eagle-import") (part "R-EU_MELF0204W"))
    )
    (comp (ref "R101")
      (value "5k")
      (footprint "eagle-import:MINI_MELF-0204W")
      (fields (field (name "SPICEPREFIX") "R"))
      (libsource (lib "eagle-import") (part "R-EU_MELF0204W"))
    )
    (comp (ref "R102")
      (value "100")
      (footprint "eagle-import:MINI_MELF-0204W")
      (fields (field (name "SPICEPREFIX") "R"))
      (libsource (lib "eagle-import") (part "R-EU_MELF0204W"))
    )
    (comp (ref "R103")
      (value "100")
      (footprint "eagle-import:MINI_MELF-0204W")
      (fields (field (name "SPICEPREFIX") "R"))
      (libsource (lib "eagle-import") (part "R-EU_MELF0204W"))
    )
    (comp (ref "R104")
      (value "100")
      (footprint "eagle-import:MINI_MELF-0204W")
      (fields (field (name "SPICEPREFIX") "R"))
      (libsource (lib "eagle-import") (part "R-EU_MELF0204W"))
    )
    (comp (ref "R105")
      (value "7k")
      (footprint "eagle-import:MINI_MELF-0204W")
      (fields (field (name "SPICEPREFIX") "R"))
      (libsource (lib "eagle-import") (part "R-EU_MELF0204W"))
    )
    (comp (ref "R106")
      (value "5k")
      (footprint "eagle-import:RTRIM3296W")
      (fields (field (name "SPICEPREFIX") "Z"))
      (libsource (lib "eagle-import") (part "R-TRIMM3296W"))
    )
    (comp (ref "R107")
      (value "1M")
      (footprint "eagle-import:MINI_MELF-0204W")
      (fields (field (name "SPICEPREFIX") "R"))
      (libsource (lib "eagle-import") (part "R-EU_MELF0204W"))
    )
    (comp (ref "R108")
      (value "1M")
      (footprint "eagle-import:MINI_MELF-0204W")
      (fields (field (name "SPICEPREFIX") "R"))
      (libsource (lib "eagle-import") (part "R-EU_MELF0204W"))
    )
    (comp (ref "R109")
      (value "1k")
      (footprint "eagle-import:MINI_MELF-0204W")
      (fields (field (name "SPICEPREFIX") "R"))
      (libsource (lib "eagle-import") (part "R-EU_MELF0204W"))
    )
    (comp (ref "R110")
      (value "220")
      (footprint "eagle-import:MINI_MELF-0204W")
      (fields (field (name "SPICEPREFIX") "R"))
      (libsource (lib "eagle-import") (part "R-EU_MELF0204W"))
    )
    (comp (ref "R111")
      (value "100k")
      (footprint "eagle-import:MINI_MELF-0204W")
      (fields (field (name "SPICEPREFIX") "R"))
      (libsource (lib "eagle-import") (part "R-EU_MELF0204W"))
    )
    (comp (ref "R112")
      (value "0.5")
      (footprint "eagle-import:R2512")
      (fields (field (name "SPICEPREFIX") "R"))
      (libsource (lib "eagle-import") (part "R-EU_R2512"))
    )
    (comp (ref "R113")
      (value "0.5")
      (footprint "eagle-import:R2512")
      (fields (field (name "SPICEPREFIX") "R"))
      (libsource (lib "eagle-import") (part "R-EU_R2512"))
    )
    (comp (ref "R114")
      (value "100k")
      (footprint "eagle-import:MINI_MELF-0204W")
      (fields (field (name "SPICEPREFIX") "R"))
      (libsource (lib "eagle-import") (part "R-EU_MELF0204W"))
    )
    (comp (ref "C1")
      (value "1000uF")
      (footprint "eagle-import:E7,5-16")
      (libsource (lib "eagle-import") (part "CPOL-EUE7.5-16"))
    )
    (comp (ref "C2")
      (value "1000uF")
      (footprint "eagle-import:E7,5-16")
      (libsource (lib "eagle-import") (part "CPOL-EUE7.5-16"))
    )
    (comp (ref "C3")
      (value "0.1uF")
      (footprint "eagle-import:C0805")
      (libsource (lib "eagle-import") (part "C-EUC0805"))
    )
    (comp (ref "C4")
      (value "0.1uF")
      (footprint "eagle-import:C0805")
      (libsource (lib "eagle-import") (part "C-EUC0805"))
    )
    (comp (ref "C6")
      (value "1000uF")
      (footprint "eagle-import:E7,5-16")
      (libsource (lib "eagle-import") (part "CPOL-EUE7.5-16"))
    )
    (comp (ref "C7")
      (value "1000uF")
      (footprint "eagle-import:E7,5-16")
      (libsource (lib "eagle-import") (part "CPOL-EUE7.5-16"))
    )
    (comp (ref "C9")
      (value "0.1uF")
      (footprint "eagle-import:C050-045X075")
      (libsource (lib "eagle-import") (part "C-EU050-045X075"))
    )
    (comp (ref "C10")
      (value "0.1uF")
      (footprint "eagle-import:C050-045X075")
      (libsource (lib "eagle-import") (part "C-EU050-045X075"))
    )
    (comp (ref "C11")
      (value "0.1uF")
      (footprint "eagle-import:C050-045X075")
      (libsource (lib "eagle-import") (part "C-EU050-045X075"))
    )
    (comp (ref "C12")
      (value "0.1uF")
      (footprint "eagle-import:C050-045X075")
      (libsource (lib "eagle-import") (part "C-EU050-045X075"))
    )
    (comp (ref "C13")
      (value "10uF")
      (footprint "eagle-import:C1206")
      (libsource (lib "eagle-import") (part "C-EUC1206"))
    )
    (comp (ref "C14")
      (value "0.1uF")
      (footprint "eagle-import:C0805")
      (libsource (lib "eagle-import") (part "C-EUC0805"))
    )
    (comp (ref "C15")
      (value "0.1uF")
      (footprint "eagle-import:C0805")
      (libsource (lib "eagle-import") (part "C-EUC0805"))
    )
    (comp (ref "C16")
      (value "10uF")
      (footprint "eagle-import:C1206")
      (libsource (lib "eagle-import") (part "C-EUC1206"))
    )
    (comp (ref "H1")
      (value "HOLE")
      (footprint "eagle-import:M3_HOLE")
      (libsource (lib "eagle-import") (part "HOLE"))
    )
    (comp (ref "H2")
      (value "HOLE")
      (footprint "eagle-import:M3_HOLE")
      (libsource (lib "eagle-import") (part "HOLE"))
    )
    (comp (ref "H3")
      (value "HOLE")
      (footprint "eagle-import:M3_HOLE")
      (libsource (lib "eagle-import") (part "HOLE"))
    )
    (comp (ref "H4")
      (value "HOLE")
      (footprint "eagle-import:M3_HOLE")
      (libsource (lib "eagle-import") (part "HOLE"))
    )
    (comp (ref "H5")
      (value "HOLE")
      (footprint "eagle-import:M3_HOLE")
      (libsource (lib "eagle-import") (part "HOLE"))
    )
    (comp (ref "H6")
      (value "HOLE")
      (footprint "eagle-import:M3_HOLE")
      (libsource (lib "eagle-import") (part "HOLE"))
    )
    (comp (ref "H7")
      (value "HOLE")
      (footprint "eagle-import:M3_HOLE")
      (libsource (lib "eagle-import") (part "HOLE"))
    )
    (comp (ref "IC1")
      (value "LTC2057HV")
      (footprint "eagle-import:SO08")
      (fields (field (name "MF") "TEXAS INSTRUMENTS") (field (name "MPN") "OPA627AU"))
      (libsource (lib "eagle-import") (part "OPA627U"))
    )
    (comp (ref "IC2")
      (value "LTC2057HV")
      (footprint "eagle-import:SO08")
      (fields (field (name "MF") "TEXAS INSTRUMENTS") (field (name "MPN") "OPA627AU"))
      (libsource (lib "eagle-import") (part "OPA627U"))
    )
    (comp (ref "LED1")
      (value "RED")
      (footprint "eagle-import:LED_SML1206")
      (libsource (lib "eagle-import") (part "LEDVWV1206"))
    )
    (comp (ref "LED2")
      (value "RED")
      (footprint "eagle-import:LED_SML1206")
      (fields (field (name "SPICEPREFIX") "D"))
      (libsource (lib "eagle-import") (part "LEDVWV1206"))
    )
    (comp (ref "LED3")
      (value "RED")
      (footprint "eagle-import:LED_SML1206")
      (libsource (lib "eagle-import") (part "LEDVWV1206"))
    )
    (comp (ref "LED4")
      (value "RED")
      (footprint "eagle-import:LED_SML1206")
      (libsource (lib "eagle-import") (part "LEDVWV1206"))
    )
    (comp (ref "LED5")
      (value "RED")
      (footprint "eagle-import:LED_SML1206")
      (libsource (lib "eagle-import") (part "LEDVWV1206"))
    )
    (comp (ref "LED6")
      (value "RED")
      (footprint "eagle-import:LED_SML1206")
      (libsource (lib "eagle-import") (part "LEDVWV1206"))
    )
    (comp (ref "LED7")
      (value "RED")
      (footprint "eagle-import:LED_SML1206")
      (libsource (lib "eagle-import") (part "LEDVWV1206"))
    )
    (comp (ref "LED8")
      (value "RED")
      (footprint "eagle-import:LED_SML1206")
      (libsource (lib "eagle-import") (part "LEDVWV1206"))
    )
    (comp (ref "Q1")
      (value "LSK689")
      (footprint "eagle-import:SOT-23-6")
      (libsource (lib "eagle-import") (part "LSK689"))
    )
    (comp (ref "Q2")
      (value "KSA992")
      (footprint "eagle-import:TRANSISTOR_TO92-ECB_P")
      (libsource (lib "eagle-import") (part "BJT_PNPKSA992"))
    )
    (comp (ref "Q3")
      (value "KSC1845")
      (footprint "eagle-import:TRANSISTOR_TO92-ECB_N")
      (libsource (lib "eagle-import") (part "BJT_NPNKSC1845"))
    )
    (comp (ref "Q4")
      (value "LSK489")
      (footprint "eagle-import:SOT-23-6")
      (libsource (lib "eagle-import") (part "LSK489SOP-6"))
    )
    (comp (ref "Q5")
      (value "KSA992")
      (footprint "eagle-import:TRANSISTOR_TO92-ECB_P")
      (libsource (lib "eagle-import") (part "BJT_PNPKSA992"))
    )
    (comp (ref "Q6")
      (value "KSC1845")
      (footprint "eagle-import:TRANSISTOR_TO92-ECB_N")
      (libsource (lib "eagle-import") (part "BJT_NPNKSC1845"))
    )
    (comp (ref "Q7")
      (value "KSC1845")
      (footprint "eagle-import:TRANSISTOR_TO92-ECB_N")
      (libsource (lib "eagle-import") (part "BJT_NPNKSC1845"))
    )
    (comp (ref "Q8")
      (value "KSA992")
      (footprint "eagle-import:TRANSISTOR_TO92-ECB_P")
      (libsource (lib "eagle-import") (part "BJT_PNPKSA992"))
    )
    (comp (ref "Q9")
      (value "KSC1845")
      (footprint "eagle-import:TRANSISTOR_TO92-ECB_N")
      (libsource (lib "eagle-import") (part "BJT_NPNKSC1845"))
    )
    (comp (ref "Q10")
      (value "KSA992")
      (footprint "eagle-import:TRANSISTOR_TO92-ECB_P")
      (libsource (lib "eagle-import") (part "BJT_PNPKSA992"))
    )
    (comp (ref "Q11")
      (value "KSA992")
      (footprint "eagle-import:TRANSISTOR_TO92-ECB_P")
      (libsource (lib "eagle-import") (part "BJT_PNPKSA992"))
    )
    (comp (ref "Q12")
      (value "KSC1845")
      (footprint "eagle-import:TRANSISTOR_TO92-ECB_N")
      (libsource (lib "eagle-import") (part "BJT_NPNKSC1845"))
    )
    (comp (ref "Q13")
      (value "KSC1845")
      (footprint "eagle-import:TRANSISTOR_TO92-ECB_N")
      (libsource (lib "eagle-import") (part "BJT_NPNKSC1845"))
    )
    (comp (ref "Q14")
      (value "KSA992")
      (footprint "eagle-import:TRANSISTOR_TO92-ECB_P")
      (libsource (lib "eagle-import") (part "BJT_PNPKSA992"))
    )
    (comp (ref "Q15")
      (value "KSC1845")
      (footprint "eagle-import:TRANSISTOR_TO92-ECB_N")
      (libsource (lib "eagle-import") (part "BJT_NPNKSC1845"))
    )
    (comp (ref "Q16")
      (value "KSA992")
      (footprint "eagle-import:TRANSISTOR_TO92-ECB_P")
      (libsource (lib "eagle-import") (part "BJT_PNPKSA992"))
    )
    (comp (ref "Q17")
      (value "KSC1845")
      (footprint "eagle-import:TRANSISTOR_TO92-ECB_N")
      (libsource (lib "eagle-import") (part "BJT_NPNKSC1845"))
    )
    (comp (ref "Q18")
      (value "KSA992")
      (footprint "eagle-import:TRANSISTOR_TO92-ECB_P")
      (libsource (lib "eagle-import") (part "BJT_PNPKSA992"))
    )
    (comp (ref "Q19")
      (value "KSA992")
      (footprint "eagle-import:TRANSISTOR_TO92-ECB_P")
      (libsource (lib "eagle-import") (part "BJT_PNPKSA992"))
    )
    (comp (ref "Q20")
      (value "KSC1845")
      (footprint "eagle-import:TRANSISTOR_TO92-ECB_N")
      (libsource (lib "eagle-import") (part "BJT_NPNKSC1845"))
    )
    (comp (ref "Q21")
      (value "KSC1845")
      (footprint "eagle-import:TRANSISTOR_TO92-ECB_N")
      (libsource (lib "eagle-import") (part "BJT_NPNKSC1845"))
    )
    (comp (ref "Q22")
      (value "KSA992")
      (footprint "eagle-import:TRANSISTOR_TO92-ECB_P")
      (libsource (lib "eagle-import") (part "BJT_PNPKSA992"))
    )
    (comp (ref "Q23")
      (value "KSC1845")
      (footprint "eagle-import:TRANSISTOR_TO92-ECB_N")
      (libsource (lib "eagle-import") (part "BJT_NPNKSC1845"))
    )
    (comp (ref "Q24")
      (value "KSA992")
      (footprint "eagle-import:TRANSISTOR_TO92-ECB_P")
      (libsource (lib "eagle-import") (part "BJT_PNPKSA992"))
    )
    (comp (ref "Q93")
      (value "KSA992")
      (footprint "eagle-import:TRANSISTOR_TO92-ECB_P")
      (libsource (lib "eagle-import") (part "BJT_PNPKSA992"))
    )
    (comp (ref "Q94")
      (value "KSA992")
      (footprint "eagle-import:TRANSISTOR_TO92-ECB_P")
      (libsource (lib "eagle-import") (part "BJT_PNPKSA992"))
    )
    (comp (ref "Q95")
      (value "KSC1845")
      (footprint "eagle-import:TRANSISTOR_TO92-ECB_N")
      (libsource (lib "eagle-import") (part "BJT_NPNKSC1845"))
    )
    (comp (ref "Q96")
      (value "KSC1845")
      (footprint "eagle-import:TRANSISTOR_TO92-ECB_N")
      (libsource (lib "eagle-import") (part "BJT_NPNKSC1845"))
    )
    (comp (ref "R1")
      (value "5k")
      (footprint "eagle-import:RTRIM3296W")
      (fields (field (name "SPICEPREFIX") "Z"))
      (libsource (lib "eagle-import") (part "R-TRIMM3296W"))
    )
    (comp (ref "R2")
      (value "10K")
      (footprint "eagle-import:MINI_MELF-0204W")
      (libsource (lib "eagle-import") (part "R-EU_MELF0204W"))
    )
    (comp (ref "R3")
      (value "10K")
      (footprint "eagle-import:MINI_MELF-0204W")
      (libsource (lib "eagle-import") (part "R-EU_MELF0204W"))
    )
    (comp (ref "R4")
      (value "10K")
      (footprint "eagle-import:MINI_MELF-0204W")
      (libsource (lib "eagle-import") (part "R-EU_MELF0204W"))
    )
    (comp (ref "R5")
      (value "250")
      (footprint "eagle-import:MINI_MELF-0204W")
      (libsource (lib "eagle-import") (part "R-EU_MELF0204W"))
    )
    (comp (ref "R6")
      (value "1K")
      (footprint "eagle-import:MINI_MELF-0204W")
      (libsource (lib "eagle-import") (part "R-EU_MELF0204W"))
    )
    (comp (ref "R7")
      (value "250")
      (footprint "eagle-import:MINI_MELF-0204W")
      (fields (field (name "SPICEPREFIX") "R"))
      (libsource (lib "eagle-import") (part "R-EU_MELF0204W"))
    )
    (comp (ref "R8")
      (value "1K")
      (footprint "eagle-import:MINI_MELF-0204W")
      (libsource (lib "eagle-import") (part "R-EU_MELF0204W"))
    )
    (comp (ref "R9")
      (value "1K")
      (footprint "eagle-import:MINI_MELF-0204W")
      (libsource (lib "eagle-import") (part "R-EU_MELF0204W"))
    )
    (comp (ref "R10")
      (value "1K")
      (footprint "eagle-import:MINI_MELF-0204W")
      (libsource (lib "eagle-import") (part "R-EU_MELF0204W"))
    )
    (comp (ref "R11")
      (value "2k")
      (footprint "eagle-import:MINI_MELF-0204W")
      (libsource (lib "eagle-import") (part "R-EU_MELF0204W"))
    )
    (comp (ref "R12")
      (value "250")
      (footprint "eagle-import:MINI_MELF-0204W")
      (libsource (lib "eagle-import") (part "R-EU_MELF0204W"))
    )
    (comp (ref "R13")
      (value "250")
      (footprint "eagle-import:MINI_MELF-0204W")
      (libsource (lib "eagle-import") (part "R-EU_MELF0204W"))
    )
    (comp (ref "R14")
      (value "10K")
      (footprint "eagle-import:MINI_MELF-0204W")
      (libsource (lib "eagle-import") (part "R-EU_MELF0204W"))
    )
    (comp (ref "R15")
      (value "10K")
      (footprint "eagle-import:MINI_MELF-0204W")
      (libsource (lib "eagle-import") (part "R-EU_MELF0204W"))
    )
    (comp (ref "R16")
      (value "10K")
      (footprint "eagle-import:MINI_MELF-0204W")
      (libsource (lib "eagle-import") (part "R-EU_MELF0204W"))
    )
    (comp (ref "R17")
      (value "10K")
      (footprint "eagle-import:MINI_MELF-0204W")
      (libsource (lib "eagle-import") (part "R-EU_MELF0204W"))
    )
    (comp (ref "R18")
      (value "250")
      (footprint "eagle-import:MINI_MELF-0204W")
      (libsource (lib "eagle-import") (part "R-EU_MELF0204W"))
    )
    (comp (ref "R19")
      (value "250")
      (footprint "eagle-import:MINI_MELF-0204W")
      (libsource (lib "eagle-import") (part "R-EU_MELF0204W"))
    )
    (comp (ref "R20")
      (value "2k")
      (footprint "eagle-import:MINI_MELF-0204W")
      (libsource (lib "eagle-import") (part "R-EU_MELF0204W"))
    )
    (comp (ref "R21")
      (value "10K")
      (footprint "eagle-import:MINI_MELF-0204W")
      (libsource (lib "eagle-import") (part "R-EU_MELF0204W"))
    )
    (comp (ref "R22")
      (value "20K")
      (footprint "eagle-import:MINI_MELF-0204W")
      (libsource (lib "eagle-import") (part "R-EU_MELF0204W"))
    )
    (comp (ref "R23")
      (value "250")
      (footprint "eagle-import:MINI_MELF-0204W")
      (libsource (lib "eagle-import") (part "R-EU_MELF0204W"))
    )
    (comp (ref "R24")
      (value "10")
      (footprint "eagle-import:MINI_MELF-0204W")
      (libsource (lib "eagle-import") (part "R-EU_MELF0204W"))
    )
    (comp (ref "R25")
      (value "10")
      (footprint "eagle-import:MINI_MELF-0204W")
      (libsource (lib "eagle-import") (part "R-EU_MELF0204W"))
    )
    (comp (ref "R26")
      (value "250")
      (footprint "eagle-import:MINI_MELF-0204W")
      (libsource (lib "eagle-import") (part "R-EU_MELF0204W"))
    )
    (comp (ref "R27")
      (value "300")
      (footprint "eagle-import:MINI_MELF-0204W")
      (libsource (lib "eagle-import") (part "R-EU_MELF0204W"))
    )
    (comp (ref "R28")
      (value "300")
      (footprint "eagle-import:MINI_MELF-0204W")
      (libsource (lib "eagle-import") (part "R-EU_MELF0204W"))
    )
    (comp (ref "R29")
      (value "10K")
      (footprint "eagle-import:MINI_MELF-0204W")
      (libsource (lib "eagle-import") (part "R-EU_MELF0204W"))
    )
    (comp (ref "R30")
      (value "10")
      (footprint "eagle-import:MINI_MELF-0204W")
      (libsource (lib "eagle-import") (part "R-EU_MELF0204W"))
    )
    (comp (ref "R31")
      (value "10")
      (footprint "eagle-import:MINI_MELF-0204W")
      (libsource (lib "eagle-import") (part "R-EU_MELF0204W"))
    )
    (comp (ref "R32")
      (value "300")
      (footprint "eagle-import:MINI_MELF-0204W")
      (libsource (lib "eagle-import") (part "R-EU_MELF0204W"))
    )
    (comp (ref "R33")
      (value "300")
      (footprint "eagle-import:MINI_MELF-0204W")
      (libsource (lib "eagle-import") (part "R-EU_MELF0204W"))
    )
    (comp (ref "R34")
      (value "10")
      (footprint "eagle-import:MINI_MELF-0204W")
      (libsource (lib "eagle-import") (part "R-EU_MELF0204W"))
    )
    (comp (ref "R35")
      (value "10")
      (footprint "eagle-import:MINI_MELF-0204W")
      (libsource (lib "eagle-import") (part "R-EU_MELF0204W"))
    )
    (comp (ref "R36")
      (value "10K")
      (footprint "eagle-import:MINI_MELF-0204W")
      (libsource (lib "eagle-import") (part "R-EU_MELF0204W"))
    )
    (comp (ref "R37")
      (value "20K")
      (footprint "eagle-import:MINI_MELF-0204W")
      (libsource (lib "eagle-import") (part "R-EU_MELF0204W"))
    )
    (comp (ref "R38")
      (value "250")
      (footprint "eagle-import:MINI_MELF-0204W")
      (libsource (lib "eagle-import") (part "R-EU_MELF0204W"))
    )
    (comp (ref "R39")
      (value "10")
      (footprint "eagle-import:MINI_MELF-0204W")
      (libsource (lib "eagle-import") (part "R-EU_MELF0204W"))
    )
    (comp (ref "R40")
      (value "10")
      (footprint "eagle-import:MINI_MELF-0204W")
      (libsource (lib "eagle-import") (part "R-EU_MELF0204W"))
    )
    (comp (ref "R41")
      (value "250")
      (footprint "eagle-import:MINI_MELF-0204W")
      (libsource (lib "eagle-import") (part "R-EU_MELF0204W"))
    )
    (comp (ref "R42")
      (value "300")
      (footprint "eagle-import:MINI_MELF-0204W")
      (libsource (lib "eagle-import") (part "R-EU_MELF0204W"))
    )
    (comp (ref "R43")
      (value "300")
      (footprint "eagle-import:MINI_MELF-0204W")
      (libsource (lib "eagle-import") (part "R-EU_MELF0204W"))
    )
    (comp (ref "R44")
      (value "10K")
      (footprint "eagle-import:MINI_MELF-0204W")
      (libsource (lib "eagle-import") (part "R-EU_MELF0204W"))
    )
    (comp (ref "R45")
      (value "10")
      (footprint "eagle-import:MINI_MELF-0204W")
      (libsource (lib "eagle-import") (part "R-EU_MELF0204W"))
    )
    (comp (ref "R46")
      (value "10")
      (footprint "eagle-import:MINI_MELF-0204W")
      (libsource (lib "eagle-import") (part "R-EU_MELF0204W"))
    )
    (comp (ref "R47")
      (value "300")
      (footprint "eagle-import:MINI_MELF-0204W")
      (libsource (lib "eagle-import") (part "R-EU_MELF0204W"))
    )
    (comp (ref "R48")
      (value "300")
      (footprint "eagle-import:MINI_MELF-0204W")
      (libsource (lib "eagle-import") (part "R-EU_MELF0204W"))
    )
    (comp (ref "R49")
      (value "10")
      (footprint "eagle-import:MINI_MELF-0204W")
      (libsource (lib "eagle-import") (part "R-EU_MELF0204W"))
    )
    (comp (ref "R50")
      (value "10")
      (footprint "eagle-import:MINI_MELF-0204W")
      (libsource (lib "eagle-import") (part "R-EU_MELF0204W"))
    )
    (comp (ref "S1")
      (value "VWV")
      (footprint "eagle-import:VWV")
      (libsource (lib "eagle-import") (part "VWV"))
    )
    (comp (ref "X1")
      (value "KK-156-3")
      (footprint "eagle-import:KK-156-3")
      (fields (field (name "MF") "MOLEX"))
      (libsource (lib "eagle-import") (part "KK-156-3"))
    )
    (comp (ref "B1")
      (value "MOS_BRIDGE")
      (footprint "eagle-import:GBU4S")
      (libsource (lib "eagle-import") (part "GBU4"))
    )
    (comp (ref "B2")
      (value "MOS_BRIDGE")
      (footprint "eagle-import:GBU4S")
      (libsource (lib "eagle-import") (part "GBU4"))
    )
    (comp (ref "C37")
      (value "10000uF")
      (footprint "eagle-import:EB35D")
      (libsource (lib "eagle-import") (part "CPOL-EUE10-35"))
    )
    (comp (ref "C38")
      (value "10000uF")
      (footprint "eagle-import:EB35D")
      (libsource (lib "eagle-import") (part "CPOL-EUE10-35"))
    )
    (comp (ref "C39")
      (value "0.1uF")
      (footprint "eagle-import:C050-075X075")
      (libsource (lib "eagle-import") (part "C-EU050-075X075"))
    )
    (comp (ref "C40")
      (value "10uF")
      (footprint "eagle-import:C1206")
      (libsource (lib "eagle-import") (part "C-EUC1206"))
    )
    (comp (ref "C41")
      (value "10uF")
      (footprint "eagle-import:C1206")
      (libsource (lib "eagle-import") (part "C-EUC1206"))
    )
    (comp (ref "C42")
      (value "0.1uF")
      (footprint "eagle-import:C050-075X075")
      (libsource (lib "eagle-import") (part "C-EU050-075X075"))
    )
    (comp (ref "C43")
      (value "0.1uF")
      (footprint "eagle-import:C0805")
      (libsource (lib "eagle-import") (part "C-EUC0805"))
    )
    (comp (ref "C44")
      (value "0.1uF")
      (footprint "eagle-import:C0805")
      (libsource (lib "eagle-import") (part "C-EUC0805"))
    )
    (comp (ref "C45")
      (value "0.1uF")
      (footprint "eagle-import:C0805")
      (libsource (lib "eagle-import") (part "C-EUC0805"))
    )
    (comp (ref "C46")
      (value "0.1uF")
      (footprint "eagle-import:C0805")
      (libsource (lib "eagle-import") (part "C-EUC0805"))
    )
    (comp (ref "C47")
      (value "10uF")
      (footprint "eagle-import:C1206")
      (libsource (lib "eagle-import") (part "C-EUC1206"))
    )
    (comp (ref "C48")
      (value "10uF")
      (footprint "eagle-import:C1206")
      (libsource (lib "eagle-import") (part "C-EUC1206"))
    )
    (comp (ref "C49")
      (value "0.1uF")
      (footprint "eagle-import:C0805")
      (libsource (lib "eagle-import") (part "C-EUC0805"))
    )
    (comp (ref "C50")
      (value "0.1uF")
      (footprint "eagle-import:C0805")
      (libsource (lib "eagle-import") (part "C-EUC0805"))
    )
    (comp (ref "C51")
      (value "47p")
      (footprint "eagle-import:C0805")
      (libsource (lib "eagle-import") (part "C-EUC0805"))
    )
    (comp (ref "C52")
      (value "47p")
      (footprint "eagle-import:C0805")
      (libsource (lib "eagle-import") (part "C-EUC0805"))
    )
    (comp (ref "C53")
      (value "10uF")
      (footprint "eagle-import:C1206")
      (libsource (lib "eagle-import") (part "C-EUC1206"))
    )
    (comp (ref "C54")
      (value "10uF")
      (footprint "eagle-import:C1206")
      (libsource (lib "eagle-import") (part "C-EUC1206"))
    )
    (comp (ref "C55")
      (value "4.7uF")
      (footprint "eagle-import:C050-075X075")
      (libsource (lib "eagle-import") (part "C-EU050-075X075"))
    )
    (comp (ref "C56")
      (value "4.7uF")
      (footprint "eagle-import:C050-075X075")
      (libsource (lib "eagle-import") (part "C-EU050-075X075"))
    )
    (comp (ref "D13")
      (value "BZT55B10")
      (footprint "eagle-import:SOD80C")
      (libsource (lib "eagle-import") (part "DIODE-SOD80C"))
    )
    (comp (ref "D14")
      (value "BZT55B10")
      (footprint "eagle-import:SOD80C")
      (libsource (lib "eagle-import") (part "DIODE-SOD80C"))
    )
    (comp (ref "D15")
      (value "S1G")
      (footprint "eagle-import:DO214AA")
      (libsource (lib "eagle-import") (part "DIODE-DO214AA"))
    )
    (comp (ref "D16")
      (value "S1G")
      (footprint "eagle-import:DO214AA")
      (libsource (lib "eagle-import") (part "DIODE-DO214AA"))
    )
    (comp (ref "D17")
      (value "LT1236-10")
      (footprint "eagle-import:SO8")
      (libsource (lib "eagle-import") (part "LINEAR-TECHNOLOGY_LT1021-VSO-8"))
    )
    (comp (ref "D18")
      (value "LT1236-10")
      (footprint "eagle-import:SO8")
      (libsource (lib "eagle-import") (part "LINEAR-TECHNOLOGY_LT1021-VSO-8"))
    )
    (comp (ref "IC5")
      (value "OPA827")
      (footprint "eagle-import:SOIC8")
      (libsource (lib "eagle-import") (part "LT10S837C"))
    )
    (comp (ref "IC6")
      (value "OPA827")
      (footprint "eagle-import:SOIC8")
      (libsource (lib "eagle-import") (part "LT10S837C"))
    )
    (comp (ref "LED13")
      (value "RED")
      (footprint "eagle-import:LED_SML1206")
      (libsource (lib "eagle-import") (part "LEDVWV1206"))
    )
    (comp (ref "LED14")
      (value "RED")
      (footprint "eagle-import:LED_SML1206")
      (libsource (lib "eagle-import") (part "LEDVWV1206"))
    )
    (comp (ref "LED15")
      (value "RED")
      (footprint "eagle-import:LED_SML1206")
      (libsource (lib "eagle-import") (part "LEDVWV1206"))
    )
    (comp (ref "LED16")
      (value "RED")
      (footprint "eagle-import:LED_SML1206")
      (libsource (lib "eagle-import") (part "LEDVWV1206"))
    )
    (comp (ref "LED17")
      (value "RED")
      (footprint "eagle-import:LED_SML1206")
      (libsource (lib "eagle-import") (part "LEDVWV1206"))
    )
    (comp (ref "LED18")
      (value "RED")
      (footprint "eagle-import:LED_SML1206")
      (libsource (lib "eagle-import") (part "LEDVWV1206"))
    )
    (comp (ref "Q79")
      (value "KSC1845")
      (footprint "eagle-import:TRANSISTOR_TO92-ECB_N")
      (libsource (lib "eagle-import") (part "BJT_NPNKSC1845"))
    )
    (comp (ref "Q80")
      (value "KSA992")
      (footprint "eagle-import:TRANSISTOR_TO92-ECB_P")
      (libsource (lib "eagle-import") (part "BJT_PNPKSA992"))
    )
    (comp (ref "Q81")
      (value "KSA992")
      (footprint "eagle-import:TRANSISTOR_TO92-ECB_P")
      (libsource (lib "eagle-import") (part "BJT_PNPKSA992"))
    )
    (comp (ref "Q82")
      (value "KSC1845")
      (footprint "eagle-import:TRANSISTOR_TO92-ECB_N")
      (libsource (lib "eagle-import") (part "BJT_NPNKSC1845"))
    )
    (comp (ref "Q83")
      (value "KSA992")
      (footprint "eagle-import:TRANSISTOR_TO92-ECB_P")
      (libsource (lib "eagle-import") (part "BJT_PNPKSA992"))
    )
    (comp (ref "Q84")
      (value "KSC1845")
      (footprint "eagle-import:TRANSISTOR_TO92-ECB_N")
      (libsource (lib "eagle-import") (part "BJT_NPNKSC1845"))
    )
    (comp (ref "Q85")
      (value "KSA992")
      (footprint "eagle-import:TRANSISTOR_TO92-ECB_P")
      (libsource (lib "eagle-import") (part "BJT_PNPKSA992"))
    )
    (comp (ref "Q86")
      (value "KSC1845")
      (footprint "eagle-import:TRANSISTOR_TO92-ECB_N")
      (libsource (lib "eagle-import") (part "BJT_NPNKSC1845"))
    )
    (comp (ref "Q87")
      (value "KSC1845")
      (footprint "eagle-import:TRANSISTOR_TO92-ECB_N")
      (libsource (lib "eagle-import") (part "BJT_NPNKSC1845"))
    )
    (comp (ref "Q88")
      (value "KSA992")
      (footprint "eagle-import:TRANSISTOR_TO92-ECB_P")
      (libsource (lib "eagle-import") (part "BJT_PNPKSA992"))
    )
    (comp (ref "Q89")
      (value "MJL4281A")
      (footprint "eagle-import:TRANSISTOR_TO247_BCE_N")
      (libsource (lib "eagle-import") (part "BJT_NPNMJL4281"))
    )
    (comp (ref "Q90")
      (value "MJL4302A")
      (footprint "eagle-import:TRANSISTOR_TO247_BCE_P")
      (libsource (lib "eagle-import") (part "BJT_PNPMJL4302"))
    )
    (comp (ref "Q91")
      (value "DN2540")
      (footprint "eagle-import:TRANSISTOR_TO92-SGD_N")
      (libsource (lib "eagle-import") (part "DN2540"))
    )
    (comp (ref "Q92")
      (value "DN2540")
      (footprint "eagle-import:TRANSISTOR_TO92-SGD_N")
      (libsource (lib "eagle-import") (part "DN2540"))
    )
    (comp (ref "R115")
      (value "10k")
      (footprint "eagle-import:MINI_MELF-0204W")
      (libsource (lib "eagle-import") (part "R-EU_MELF0204W"))
    )
    (comp (ref "R116")
      (value "10k")
      (footprint "eagle-import:MINI_MELF-0204W")
      (libsource (lib "eagle-import") (part "R-EU_MELF0204W"))
    )
    (comp (ref "R117")
      (value "1k")
      (footprint "eagle-import:MINI_MELF-0204W")
      (libsource (lib "eagle-import") (part "R-EU_MELF0204W"))
    )
    (comp (ref "R118")
      (value "1k")
      (footprint "eagle-import:MINI_MELF-0204W")
      (libsource (lib "eagle-import") (part "R-EU_MELF0204W"))
    )
    (comp (ref "R119")
      (value "100")
      (footprint "eagle-import:MINI_MELF-0204W")
      (libsource (lib "eagle-import") (part "R-EU_MELF0204W"))
    )
    (comp (ref "R120")
      (value "10")
      (footprint "eagle-import:MINI_MELF-0204W")
      (libsource (lib "eagle-import") (part "R-EU_MELF0204W"))
    )
    (comp (ref "R121")
      (value "10")
      (footprint "eagle-import:MINI_MELF-0204W")
      (libsource (lib "eagle-import") (part "R-EU_MELF0204W"))
    )
    (comp (ref "R122")
      (value "100")
      (footprint "eagle-import:MINI_MELF-0204W")
      (libsource (lib "eagle-import") (part "R-EU_MELF0204W"))
    )
    (comp (ref "R123")
      (value "10")
      (footprint "eagle-import:MINI_MELF-0204W")
      (libsource (lib "eagle-import") (part "R-EU_MELF0204W"))
    )
    (comp (ref "R124")
      (value "10")
      (footprint "eagle-import:MINI_MELF-0204W")
      (libsource (lib "eagle-import") (part "R-EU_MELF0204W"))
    )
    (comp (ref "R125")
      (value "1k")
      (footprint "eagle-import:MINI_MELF-0204W")
      (libsource (lib "eagle-import") (part "R-EU_MELF0204W"))
    )
    (comp (ref "R126")
      (value "1k")
      (footprint "eagle-import:MINI_MELF-0204W")
      (libsource (lib "eagle-import") (part "R-EU_MELF0204W"))
    )
    (comp (ref "R127")
      (value "1.5k")
      (footprint "eagle-import:MINI_MELF-0204W")
      (libsource (lib "eagle-import") (part "R-EU_MELF0204W"))
    )
    (comp (ref "R128")
      (value "1.5k")
      (footprint "eagle-import:MINI_MELF-0204W")
      (libsource (lib "eagle-import") (part "R-EU_MELF0204W"))
    )
    (comp (ref "R129")
      (value "1.5k")
      (footprint "eagle-import:MINI_MELF-0204W")
      (libsource (lib "eagle-import") (part "R-EU_MELF0204W"))
    )
    (comp (ref "R130")
      (value "1.5k")
      (footprint "eagle-import:MINI_MELF-0204W")
      (libsource (lib "eagle-import") (part "R-EU_MELF0204W"))
    )
    (comp (ref "R131")
      (value "10k")
      (footprint "eagle-import:MINI_MELF-0204W")
      (libsource (lib "eagle-import") (part "R-EU_MELF0204W"))
    )
    (comp (ref "R132")
      (value "10k")
      (footprint "eagle-import:MINI_MELF-0204W")
      (libsource (lib "eagle-import") (part "R-EU_MELF0204W"))
    )
    (comp (ref "X3")
      (value "KK-156-2")
      (footprint "eagle-import:KK-156-2")
      (fields (field (name "MF") "MOLEX"))
      (libsource (lib "eagle-import") (part "KK-156-2"))
    )
    (comp (ref "X4")
      (value "KK-156-2")
      (footprint "eagle-import:KK-156-2")
      (fields (field (name "MF") "MOLEX"))
      (libsource (lib "eagle-import") (part "KK-156-2"))
    )
  )
  (nets
    (net (code "1") (name "BOUT+") (class "Default")
      (node (ref "R29") (pin "1") (pinfunction "1_1") (pintype "passive"))
      (node (ref "R30") (pin "1") (pinfunction "1_1") (pintype "passive"))
      (node (ref "R31") (pin "2") (pinfunction "2_2") (pintype "passive"))
      (node (ref "R34") (pin "1") (pinfunction "1_1") (pintype "passive"))
      (node (ref "R35") (pin "2") (pinfunction "2_2") (pintype "passive"))
      (node (ref "R51") (pin "2") (pinfunction "2_2") (pintype "passive"))
    )
    (net (code "2") (name "BOUT-") (class "Default")
      (node (ref "R44") (pin "1") (pinfunction "1_1") (pintype "passive"))
      (node (ref "R45") (pin "1") (pinfunction "1_1") (pintype "passive"))
      (node (ref "R46") (pin "2") (pinfunction "2_2") (pintype "passive"))
      (node (ref "R49") (pin "1") (pinfunction "1_1") (pintype "passive"))
      (node (ref "R50") (pin "2") (pinfunction "2_2") (pintype "passive"))
      (node (ref "R83") (pin "2") (pinfunction "2_2") (pintype "passive"))
    )
    (net (code "3") (name "GND") (class "Default")
      (node (ref "B1") (pin "-") (pinfunction "-_-") (pintype "passive"))
      (node (ref "B2") (pin "+") (pinfunction "+_+") (pintype "passive"))
      (node (ref "C1") (pin "-") (pinfunction "-_-") (pintype "passive"))
      (node (ref "C10") (pin "1") (pinfunction "1_1") (pintype "passive"))
      (node (ref "C11") (pin "2") (pinfunction "2_2") (pintype "passive"))
      (node (ref "C12") (pin "1") (pinfunction "1_1") (pintype "passive"))
      (node (ref "C14") (pin "1") (pinfunction "1_1") (pintype "passive"))
      (node (ref "C15") (pin "2") (pinfunction "2_2") (pintype "passive"))
      (node (ref "C17") (pin "2") (pinfunction "2_2") (pintype "passive"))
      (node (ref "C19") (pin "1") (pinfunction "1_1") (pintype "passive"))
      (node (ref "C2") (pin "+") (pinfunction "+_+") (pintype "passive"))
      (node (ref "C20") (pin "2") (pinfunction "2_2") (pintype "passive"))
      (node (ref "C22") (pin "1") (pinfunction "1_1") (pintype "passive"))
      (node (ref "C23") (pin "2") (pinfunction "2_2") (pintype "passive"))
      (node (ref "C24") (pin "1") (pinfunction "1_1") (pintype "passive"))
      (node (ref "C25") (pin "-") (pinfunction "-_-") (pintype "passive"))
      (node (ref "C26") (pin "+") (pinfunction "+_+") (pintype "passive"))
      (node (ref "C27") (pin "2") (pinfunction "2_2") (pintype "passive"))
      (node (ref "C29") (pin "1") (pinfunction "1_1") (pintype "passive"))
      (node (ref "C3") (pin "1") (pinfunction "1_1") (pintype "passive"))
      (node (ref "C30") (pin "2") (pinfunction "2_2") (pintype "passive"))
      (node (ref "C32") (pin "1") (pinfunction "1_1") (pintype "passive"))
      (node (ref "C33") (pin "2") (pinfunction "2_2") (pintype "passive"))
      (node (ref "C34") (pin "1") (pinfunction "1_1") (pintype "passive"))
      (node (ref "C35") (pin "-") (pinfunction "-_-") (pintype "passive"))
      (node (ref "C36") (pin "+") (pinfunction "+_+") (pintype "passive"))
      (node (ref "C37") (pin "-") (pinfunction "-_-") (pintype "passive"))
      (node (ref "C38") (pin "+") (pinfunction "+_+") (pintype "passive"))
      (node (ref "C39") (pin "1") (pinfunction "1_1") (pintype "passive"))
      (node (ref "C4") (pin "2") (pinfunction "2_2") (pintype "passive"))
      (node (ref "C42") (pin "2") (pinfunction "2_2") (pintype "passive"))
      (node (ref "C45") (pin "1") (pinfunction "1_1") (pintype "passive"))
      (node (ref "C46") (pin "2") (pinfunction "2_2") (pintype "passive"))
      (node (ref "C47") (pin "2") (pinfunction "2_2") (pintype "passive"))
      (node (ref "C48") (pin "1") (pinfunction "1_1") (pintype "passive"))
      (node (ref "C49") (pin "2") (pinfunction "2_2") (pintype "passive"))
      (node (ref "C50") (pin "1") (pinfunction "1_1") (pintype "passive"))
      (node (ref "C55") (pin "1") (pinfunction "1_1") (pintype "passive"))
      (node (ref "C56") (pin "2") (pinfunction "2_2") (pintype "passive"))
      (node (ref "C6") (pin "+") (pinfunction "+_+") (pintype "passive"))
      (node (ref "C7") (pin "-") (pinfunction "-_-") (pintype "passive"))
      (node (ref "C9") (pin "2") (pinfunction "2_2") (pintype "passive"))
      (node (ref "D17") (pin "4") (pinfunction "GND_4") (pintype "passive"))
      (node (ref "D18") (pin "6") (pinfunction "OUT_6") (pintype "passive"))
      (node (ref "IC1") (pin "3") (pinfunction "+IN_3") (pintype "input"))
      (node (ref "IC2") (pin "3") (pinfunction "+IN_3") (pintype "input"))
      (node (ref "IC5") (pin "7") (pinfunction "V+_7") (pintype "power_in"))
      (node (ref "IC6") (pin "4") (pinfunction "V-_4") (pintype "power_in"))
      (node (ref "LED13") (pin "C") (pinfunction "C_C") (pintype "passive"))
      (node (ref "LED14") (pin "A") (pinfunction "A_A") (pintype "passive"))
      (node (ref "LED17") (pin "C") (pinfunction "C_C") (pintype "passive"))
      (node (ref "LED18") (pin "A") (pinfunction "A_A") (pintype "passive"))
      (node (ref "Q85") (pin "C") (pinfunction "C_C") (pintype "passive"))
      (node (ref "Q86") (pin "C") (pinfunction "C_C") (pintype "passive"))
      (node (ref "R107") (pin "2") (pinfunction "2_2") (pintype "passive"))
      (node (ref "R108") (pin "1") (pinfunction "1_1") (pintype "passive"))
      (node (ref "R11") (pin "1") (pinfunction "1_1") (pintype "passive"))
      (node (ref "R111") (pin "1") (pinfunction "1_1") (pintype "passive"))
      (node (ref "R117") (pin "2") (pinfunction "2_2") (pintype "passive"))
      (node (ref "R118") (pin "1") (pinfunction "1_1") (pintype "passive"))
      (node (ref "R128") (pin "1") (pinfunction "1_1") (pintype "passive"))
      (node (ref "R129") (pin "2") (pinfunction "2_2") (pintype "passive"))
      (node (ref "R15") (pin "1") (pinfunction "1_1") (pintype "passive"))
      (node (ref "R16") (pin "2") (pinfunction "2_2") (pintype "passive"))
      (node (ref "R20") (pin "1") (pinfunction "1_1") (pintype "passive"))
      (node (ref "R52") (pin "1") (pinfunction "1_1") (pintype "passive"))
      (node (ref "R63") (pin "1") (pinfunction "1_1") (pintype "passive"))
      (node (ref "R75") (pin "2") (pinfunction "2_2") (pintype "passive"))
      (node (ref "R76") (pin "1") (pinfunction "1_1") (pintype "passive"))
      (node (ref "R79") (pin "1") (pinfunction "1_1") (pintype "passive"))
      (node (ref "R84") (pin "1") (pinfunction "1_1") (pintype "passive"))
      (node (ref "R95") (pin "1") (pinfunction "1_1") (pintype "passive"))
      (node (ref "X1") (pin "2") (pinfunction "S_2") (pintype "passive"))
    )
    (net (code "4") (name "IN+") (class "Default")
      (node (ref "Q1") (pin "1") (pinfunction "G_1") (pintype "passive"))
      (node (ref "Q4") (pin "1") (pinfunction "G_1") (pintype "passive"))
      (node (ref "X1") (pin "1") (pinfunction "S_1") (pintype "passive"))
    )
    (net (code "5") (name "IN-") (class "Default")
      (node (ref "Q1") (pin "4") (pinfunction "G_4") (pintype "passive"))
      (node (ref "Q4") (pin "4") (pinfunction "G_4") (pintype "passive"))
      (node (ref "X1") (pin "3") (pinfunction "S_3") (pintype "passive"))
    )
    (net (code "6") (name "Net-(B1-AC1)") (class "Default")
      (node (ref "B1") (pin "AC2") (pinfunction "AC1_AC2") (pintype "passive"))
      (node (ref "X3") (pin "1") (pinfunction "S_1") (pintype "passive"))
    )
    (net (code "7") (name "Net-(B1-AC2)") (class "Default")
      (node (ref "B1") (pin "AC1") (pinfunction "AC2_AC1") (pintype "passive"))
      (node (ref "X3") (pin "2") (pinfunction "S_2") (pintype "passive"))
    )
    (net (code "8") (name "Net-(B1-Pad+)") (class "Default")
      (node (ref "B1") (pin "+") (pinfunction "+_+") (pintype "passive"))
      (node (ref "C37") (pin "+") (pinfunction "+_+") (pintype "passive"))
      (node (ref "C42") (pin "1") (pinfunction "1_1") (pintype "passive"))
      (node (ref "D15") (pin "C") (pinfunction "C_C") (pintype "passive"))
      (node (ref "LED15") (pin "A") (pinfunction "A_A") (pintype "passive"))
      (node (ref "Q87") (pin "C") (pinfunction "C_C") (pintype "passive"))
      (node (ref "Q89") (pin "C") (pinfunction "C_C") (pintype "passive"))
      (node (ref "R115") (pin "1") (pinfunction "1_1") (pintype "passive"))
      (node (ref "R119") (pin "1") (pinfunction "1_1") (pintype "passive"))
    )
    (net (code "9") (name "Net-(B2-AC1)") (class "Default")
      (node (ref "B2") (pin "AC2") (pinfunction "AC1_AC2") (pintype "passive"))
      (node (ref "X4") (pin "2") (pinfunction "S_2") (pintype "passive"))
    )
    (net (code "10") (name "Net-(B2-AC2)") (class "Default")
      (node (ref "B2") (pin "AC1") (pinfunction "AC2_AC1") (pintype "passive"))
      (node (ref "X4") (pin "1") (pinfunction "S_1") (pintype "passive"))
    )
    (net (code "11") (name "Net-(B2-Pad-)") (class "Default")
      (node (ref "B2") (pin "-") (pinfunction "-_-") (pintype "passive"))
      (node (ref "C38") (pin "-") (pinfunction "-_-") (pintype "passive"))
      (node (ref "C39") (pin "2") (pinfunction "2_2") (pintype "passive"))
      (node (ref "D16") (pin "A") (pinfunction "A_A") (pintype "passive"))
      (node (ref "LED16") (pin "C") (pinfunction "C_C") (pintype "passive"))
      (node (ref "Q88") (pin "C") (pinfunction "C_C") (pintype "passive"))
      (node (ref "Q90") (pin "C") (pinfunction "C_C") (pintype "passive"))
      (node (ref "R116") (pin "2") (pinfunction "2_2") (pintype "passive"))
      (node (ref "R122") (pin "2") (pinfunction "2_2") (pintype "passive"))
    )
    (net (code "12") (name "Net-(C17-Pad1)") (class "Default")
      (node (ref "C17") (pin "1") (pinfunction "1_1") (pintype "passive"))
      (node (ref "Q26") (pin "B") (pinfunction "B_B") (pintype "passive"))
      (node (ref "Q27") (pin "B") (pinfunction "B_B") (pintype "passive"))
      (node (ref "R51") (pin "1") (pinfunction "1_1") (pintype "passive"))
      (node (ref "R52") (pin "2") (pinfunction "2_2") (pintype "passive"))
    )
    (net (code "13") (name "Net-(C18-Pad1)") (class "Default")
      (node (ref "C18") (pin "1") (pinfunction "1_1") (pintype "passive"))
      (node (ref "C19") (pin "2") (pinfunction "2_2") (pintype "passive"))
      (node (ref "Q39") (pin "C") (pinfunction "C_C") (pintype "passive"))
      (node (ref "Q43") (pin "C") (pinfunction "C_C") (pintype "passive"))
      (node (ref "Q45") (pin "C") (pinfunction "C_C") (pintype "passive"))
      (node (ref "Q46") (pin "B") (pinfunction "B_B") (pintype "passive"))
      (node (ref "R73") (pin "2") (pinfunction "2_2") (pintype "passive"))
      (node (ref "R75") (pin "1") (pinfunction "1_1") (pintype "passive"))
    )
    (net (code "14") (name "Net-(C27-Pad1)") (class "Default")
      (node (ref "C27") (pin "1") (pinfunction "1_1") (pintype "passive"))
      (node (ref "Q53") (pin "B") (pinfunction "B_B") (pintype "passive"))
      (node (ref "Q54") (pin "B") (pinfunction "B_B") (pintype "passive"))
      (node (ref "R83") (pin "1") (pinfunction "1_1") (pintype "passive"))
      (node (ref "R84") (pin "2") (pinfunction "2_2") (pintype "passive"))
    )
    (net (code "15") (name "Net-(C28-Pad1)") (class "Default")
      (node (ref "C28") (pin "1") (pinfunction "1_1") (pintype "passive"))
      (node (ref "C29") (pin "2") (pinfunction "2_2") (pintype "passive"))
      (node (ref "Q66") (pin "C") (pinfunction "C_C") (pintype "passive"))
      (node (ref "Q70") (pin "C") (pinfunction "C_C") (pintype "passive"))
      (node (ref "Q72") (pin "C") (pinfunction "C_C") (pintype "passive"))
      (node (ref "Q73") (pin "B") (pinfunction "B_B") (pintype "passive"))
      (node (ref "R105") (pin "2") (pinfunction "2_2") (pintype "passive"))
      (node (ref "R107") (pin "1") (pinfunction "1_1") (pintype "passive"))
    )
    (net (code "16") (name "Net-(C40-Pad1)") (class "Default")
      (node (ref "C40") (pin "1") (pinfunction "1_1") (pintype "passive"))
      (node (ref "C43") (pin "1") (pinfunction "1_1") (pintype "passive"))
      (node (ref "D13") (pin "C") (pinfunction "C_C") (pintype "passive"))
      (node (ref "Q83") (pin "C") (pinfunction "C_C") (pintype "passive"))
      (node (ref "Q87") (pin "B") (pinfunction "B_B") (pintype "passive"))
    )
    (net (code "17") (name "Net-(C40-Pad2)") (class "Default")
      (node (ref "C40") (pin "2") (pinfunction "2_2") (pintype "passive"))
      (node (ref "C43") (pin "2") (pinfunction "2_2") (pintype "passive"))
      (node (ref "D13") (pin "A") (pinfunction "A_A") (pintype "passive"))
      (node (ref "R120") (pin "1") (pinfunction "1_1") (pintype "passive"))
    )
    (net (code "18") (name "Net-(C41-Pad1)") (class "Default")
      (node (ref "C41") (pin "1") (pinfunction "1_1") (pintype "passive"))
      (node (ref "C44") (pin "1") (pinfunction "1_1") (pintype "passive"))
      (node (ref "D14") (pin "C") (pinfunction "C_C") (pintype "passive"))
      (node (ref "R121") (pin "2") (pinfunction "2_2") (pintype "passive"))
    )
    (net (code "19") (name "Net-(C41-Pad2)") (class "Default")
      (node (ref "C41") (pin "2") (pinfunction "2_2") (pintype "passive"))
      (node (ref "C44") (pin "2") (pinfunction "2_2") (pintype "passive"))
      (node (ref "D14") (pin "A") (pinfunction "A_A") (pintype "passive"))
      (node (ref "Q84") (pin "C") (pinfunction "C_C") (pintype "passive"))
      (node (ref "Q88") (pin "B") (pinfunction "B_B") (pintype "passive"))
    )
    (net (code "20") (name "Net-(D1-PadC)") (class "Default")
      (node (ref "D1") (pin "C") (pinfunction "C_C") (pintype "passive"))
      (node (ref "D2") (pin "A") (pinfunction "A_A") (pintype "passive"))
    )
    (net (code "21") (name "Net-(D2-PadC)") (class "Default")
      (node (ref "D2") (pin "C") (pinfunction "C_C") (pintype "passive"))
      (node (ref "Q25") (pin "B") (pinfunction "B_B") (pintype "passive"))
      (node (ref "R53") (pin "2") (pinfunction "2_2") (pintype "passive"))
    )
    (net (code "22") (name "Net-(D3-PadA)") (class "Default")
      (node (ref "D3") (pin "A") (pinfunction "A_A") (pintype "passive"))
      (node (ref "Q28") (pin "B") (pinfunction "B_B") (pintype "passive"))
      (node (ref "R53") (pin "1") (pinfunction "1_1") (pintype "passive"))
    )
    (net (code "23") (name "Net-(D3-PadC)") (class "Default")
      (node (ref "D3") (pin "C") (pinfunction "C_C") (pintype "passive"))
      (node (ref "D4") (pin "A") (pinfunction "A_A") (pintype "passive"))
    )
    (net (code "24") (name "Net-(D5-PadA)") (class "Default")
      (node (ref "D5") (pin "A") (pinfunction "A_A") (pintype "passive"))
      (node (ref "Q25") (pin "C") (pinfunction "C_C") (pintype "passive"))
      (node (ref "Q29") (pin "B") (pinfunction "B_B") (pintype "passive"))
    )
    (net (code "25") (name "Net-(D5-PadC)") (class "Default")
      (node (ref "D5") (pin "C") (pinfunction "C_C") (pintype "passive"))
      (node (ref "Q30") (pin "B") (pinfunction "B_B") (pintype "passive"))
      (node (ref "R55") (pin "2") (pinfunction "2_2") (pintype "passive"))
    )
    (net (code "26") (name "Net-(D6-PadA)") (class "Default")
      (node (ref "D6") (pin "A") (pinfunction "A_A") (pintype "passive"))
      (node (ref "Q31") (pin "B") (pinfunction "B_B") (pintype "passive"))
      (node (ref "R56") (pin "1") (pinfunction "1_1") (pintype "passive"))
    )
    (net (code "27") (name "Net-(D6-PadC)") (class "Default")
      (node (ref "D6") (pin "C") (pinfunction "C_C") (pintype "passive"))
      (node (ref "Q28") (pin "C") (pinfunction "C_C") (pintype "passive"))
      (node (ref "Q32") (pin "B") (pinfunction "B_B") (pintype "passive"))
    )
    (net (code "28") (name "Net-(D7-PadC)") (class "Default")
      (node (ref "D7") (pin "C") (pinfunction "C_C") (pintype "passive"))
      (node (ref "D8") (pin "A") (pinfunction "A_A") (pintype "passive"))
    )
    (net (code "29") (name "Net-(D8-PadC)") (class "Default")
      (node (ref "D8") (pin "C") (pinfunction "C_C") (pintype "passive"))
      (node (ref "Q52") (pin "B") (pinfunction "B_B") (pintype "passive"))
      (node (ref "R85") (pin "2") (pinfunction "2_2") (pintype "passive"))
    )
    (net (code "30") (name "Net-(D9-PadA)") (class "Default")
      (node (ref "D9") (pin "A") (pinfunction "A_A") (pintype "passive"))
      (node (ref "Q55") (pin "B") (pinfunction "B_B") (pintype "passive"))
      (node (ref "R85") (pin "1") (pinfunction "1_1") (pintype "passive"))
    )
    (net (code "31") (name "Net-(D10-PadA)") (class "Default")
      (node (ref "D10") (pin "A") (pinfunction "A_A") (pintype "passive"))
      (node (ref "D9") (pin "C") (pinfunction "C_C") (pintype "passive"))
    )
    (net (code "32") (name "Net-(D11-PadA)") (class "Default")
      (node (ref "D11") (pin "A") (pinfunction "A_A") (pintype "passive"))
      (node (ref "Q52") (pin "C") (pinfunction "C_C") (pintype "passive"))
      (node (ref "Q56") (pin "B") (pinfunction "B_B") (pintype "passive"))
    )
    (net (code "33") (name "Net-(D11-PadC)") (class "Default")
      (node (ref "D11") (pin "C") (pinfunction "C_C") (pintype "passive"))
      (node (ref "Q57") (pin "B") (pinfunction "B_B") (pintype "passive"))
      (node (ref "R87") (pin "2") (pinfunction "2_2") (pintype "passive"))
    )
    (net (code "34") (name "Net-(D12-PadA)") (class "Default")
      (node (ref "D12") (pin "A") (pinfunction "A_A") (pintype "passive"))
      (node (ref "Q58") (pin "B") (pinfunction "B_B") (pintype "passive"))
      (node (ref "R88") (pin "1") (pinfunction "1_1") (pintype "passive"))
    )
    (net (code "35") (name "Net-(D12-PadC)") (class "Default")
      (node (ref "D12") (pin "C") (pinfunction "C_C") (pintype "passive"))
      (node (ref "Q55") (pin "C") (pinfunction "C_C") (pintype "passive"))
      (node (ref "Q59") (pin "B") (pinfunction "B_B") (pintype "passive"))
    )
    (net (code "36") (name "Net-(D17-OUT)") (class "Default")
      (node (ref "C47") (pin "1") (pinfunction "1_1") (pintype "passive"))
      (node (ref "C49") (pin "1") (pinfunction "1_1") (pintype "passive"))
      (node (ref "D17") (pin "6") (pinfunction "OUT_6") (pintype "passive"))
      (node (ref "IC6") (pin "3") (pinfunction "+IN_3") (pintype "input"))
      (node (ref "Q91") (pin "G") (pinfunction "G_G") (pintype "passive"))
      (node (ref "R125") (pin "1") (pinfunction "1_1") (pintype "passive"))
    )
    (net (code "37") (name "Net-(D18-GND)") (class "Default")
      (node (ref "C48") (pin "2") (pinfunction "2_2") (pintype "passive"))
      (node (ref "C50") (pin "2") (pinfunction "2_2") (pintype "passive"))
      (node (ref "D18") (pin "4") (pinfunction "GND_4") (pintype "passive"))
      (node (ref "IC5") (pin "3") (pinfunction "+IN_3") (pintype "input"))
      (node (ref "Q92") (pin "D") (pinfunction "D_D") (pintype "passive"))
    )
    (net (code "38") (name "Net-(IC1--IN)") (class "Default")
      (node (ref "C13") (pin "2") (pinfunction "2_2") (pintype "passive"))
      (node (ref "IC1") (pin "2") (pinfunction "-IN_2") (pintype "input"))
      (node (ref "R29") (pin "2") (pinfunction "2_2") (pintype "passive"))
    )
    (net (code "39") (name "Net-(IC1-OUT)") (class "Default")
      (node (ref "C13") (pin "1") (pinfunction "1_1") (pintype "passive"))
      (node (ref "IC1") (pin "6") (pinfunction "OUT_6") (pintype "output"))
      (node (ref "R21") (pin "1") (pinfunction "1_1") (pintype "passive"))
    )
    (net (code "40") (name "Net-(IC2--IN)") (class "Default")
      (node (ref "C16") (pin "2") (pinfunction "2_2") (pintype "passive"))
      (node (ref "IC2") (pin "2") (pinfunction "-IN_2") (pintype "input"))
      (node (ref "R44") (pin "2") (pinfunction "2_2") (pintype "passive"))
    )
    (net (code "41") (name "Net-(IC2-OUT)") (class "Default")
      (node (ref "C16") (pin "1") (pinfunction "1_1") (pintype "passive"))
      (node (ref "IC2") (pin "6") (pinfunction "OUT_6") (pintype "output"))
      (node (ref "R36") (pin "1") (pinfunction "1_1") (pintype "passive"))
    )
    (net (code "42") (name "Net-(IC3-+IN)") (class "Default")
      (node (ref "C22") (pin "2") (pinfunction "2_2") (pintype "passive"))
      (node (ref "IC3") (pin "3") (pinfunction "+IN_3") (pintype "input"))
      (node (ref "R82") (pin "2") (pinfunction "2_2") (pintype "passive"))
    )
    (net (code "43") (name "Net-(IC3--IN)") (class "Default")
      (node (ref "C21") (pin "2") (pinfunction "2_2") (pintype "passive"))
      (node (ref "IC3") (pin "2") (pinfunction "-IN_2") (pintype "input"))
      (node (ref "R79") (pin "2") (pinfunction "2_2") (pintype "passive"))
    )
    (net (code "44") (name "Net-(IC3-OUT)") (class "Default")
      (node (ref "C21") (pin "1") (pinfunction "1_1") (pintype "passive"))
      (node (ref "IC3") (pin "6") (pinfunction "OUT_6") (pintype "output"))
      (node (ref "R68") (pin "1") (pinfunction "1_1") (pintype "passive"))
      (node (ref "R69") (pin "2") (pinfunction "2_2") (pintype "passive"))
    )
    (net (code "45") (name "Net-(IC4-+IN)") (class "Default")
      (node (ref "C32") (pin "2") (pinfunction "2_2") (pintype "passive"))
      (node (ref "IC4") (pin "3") (pinfunction "+IN_3") (pintype "input"))
      (node (ref "R114") (pin "2") (pinfunction "2_2") (pintype "passive"))
    )
    (net (code "46") (name "Net-(IC4--IN)") (class "Default")
      (node (ref "C31") (pin "2") (pinfunction "2_2") (pintype "passive"))
      (node (ref "IC4") (pin "2") (pinfunction "-IN_2") (pintype "input"))
      (node (ref "R111") (pin "2") (pinfunction "2_2") (pintype "passive"))
    )
    (net (code "47") (name "Net-(IC4-OUT)") (class "Default")
      (node (ref "C31") (pin "1") (pinfunction "1_1") (pintype "passive"))
      (node (ref "IC4") (pin "6") (pinfunction "OUT_6") (pintype "output"))
      (node (ref "R100") (pin "1") (pinfunction "1_1") (pintype "passive"))
      (node (ref "R101") (pin "2") (pinfunction "2_2") (pintype "passive"))
    )
    (net (code "48") (name "Net-(IC5--IN)") (class "Default")
      (node (ref "C52") (pin "2") (pinfunction "2_2") (pintype "passive"))
      (node (ref "C54") (pin "1") (pinfunction "1_1") (pintype "passive"))
      (node (ref "IC5") (pin "2") (pinfunction "-IN_2") (pintype "input"))
      (node (ref "R129") (pin "1") (pinfunction "1_1") (pintype "passive"))
      (node (ref "R130") (pin "2") (pinfunction "2_2") (pintype "passive"))
    )
    (net (code "49") (name "Net-(IC5-OUT)") (class "Default")
      (node (ref "C52") (pin "1") (pinfunction "1_1") (pintype "passive"))
      (node (ref "IC5") (pin "6") (pinfunction "OUT_6") (pintype "output"))
      (node (ref "R124") (pin "1") (pinfunction "1_1") (pintype "passive"))
    )
    (net (code "50") (name "Net-(IC6--IN)") (class "Default")
      (node (ref "C51") (pin "2") (pinfunction "2_2") (pintype "passive"))
      (node (ref "C53") (pin "2") (pinfunction "2_2") (pintype "passive"))
      (node (ref "IC6") (pin "2") (pinfunction "-IN_2") (pintype "input"))
      (node (ref "R127") (pin "1") (pinfunction "1_1") (pintype "passive"))
      (node (ref "R128") (pin "2") (pinfunction "2_2") (pintype "passive"))
    )
    (net (code "51") (name "Net-(IC6-OUT)") (class "Default")
      (node (ref "C51") (pin "1") (pinfunction "1_1") (pintype "passive"))
      (node (ref "IC6") (pin "6") (pinfunction "OUT_6") (pintype "output"))
      (node (ref "R123") (pin "1") (pinfunction "1_1") (pintype "passive"))
    )
    (net (code "52") (name "Net-(LED1-PadC)") (class "Default")
      (node (ref "LED1") (pin "C") (pinfunction "C_C") (pintype "passive"))
      (node (ref "Q2") (pin "B") (pinfunction "B_B") (pintype "passive"))
      (node (ref "R3") (pin "2") (pinfunction "2_2") (pintype "passive"))
    )
    (net (code "53") (name "Net-(LED2-PadA)") (class "Default")
      (node (ref "LED2") (pin "A") (pinfunction "A_A") (pintype "passive"))
      (node (ref "Q3") (pin "B") (pinfunction "B_B") (pintype "passive"))
      (node (ref "R4") (pin "1") (pinfunction "1_1") (pintype "passive"))
    )
    (net (code "54") (name "Net-(LED3-PadC)") (class "Default")
      (node (ref "LED3") (pin "C") (pinfunction "C_C") (pintype "passive"))
      (node (ref "Q5") (pin "B") (pinfunction "B_B") (pintype "passive"))
      (node (ref "Q93") (pin "B") (pinfunction "B_B") (pintype "passive"))
      (node (ref "R14") (pin "2") (pinfunction "2_2") (pintype "passive"))
    )
    (net (code "55") (name "Net-(LED4-PadA)") (class "Default")
      (node (ref "LED4") (pin "A") (pinfunction "A_A") (pintype "passive"))
      (node (ref "Q95") (pin "B") (pinfunction "B_B") (pintype "passive"))
      (node (ref "Q96") (pin "B") (pinfunction "B_B") (pintype "passive"))
      (node (ref "R17") (pin "1") (pinfunction "1_1") (pintype "passive"))
    )
    (net (code "56") (name "Net-(LED5-PadC)") (class "Default")
      (node (ref "LED5") (pin "C") (pinfunction "C_C") (pintype "passive"))
      (node (ref "Q11") (pin "B") (pinfunction "B_B") (pintype "passive"))
      (node (ref "R22") (pin "2") (pinfunction "2_2") (pintype "passive"))
    )
    (net (code "57") (name "Net-(LED6-PadA)") (class "Default")
      (node (ref "LED6") (pin "A") (pinfunction "A_A") (pintype "passive"))
      (node (ref "Q12") (pin "B") (pinfunction "B_B") (pintype "passive"))
      (node (ref "R22") (pin "1") (pinfunction "1_1") (pintype "passive"))
    )
    (net (code "58") (name "Net-(LED7-PadC)") (class "Default")
      (node (ref "LED7") (pin "C") (pinfunction "C_C") (pintype "passive"))
      (node (ref "Q19") (pin "B") (pinfunction "B_B") (pintype "passive"))
      (node (ref "R37") (pin "2") (pinfunction "2_2") (pintype "passive"))
    )
    (net (code "59") (name "Net-(LED8-PadA)") (class "Default")
      (node (ref "LED8") (pin "A") (pinfunction "A_A") (pintype "passive"))
      (node (ref "Q20") (pin "B") (pinfunction "B_B") (pintype "passive"))
      (node (ref "R37") (pin "1") (pinfunction "1_1") (pintype "passive"))
    )
    (net (code "60") (name "Net-(LED9-PadA)") (class "Default")
      (node (ref "LED9") (pin "A") (pinfunction "A_A") (pintype "passive"))
      (node (ref "Q35") (pin "E") (pinfunction "E_E") (pintype "passive"))
      (node (ref "R62") (pin "1") (pinfunction "1_1") (pintype "passive"))
    )
    (net (code "61") (name "Net-(LED9-PadC)") (class "Default")
      (node (ref "LED9") (pin "C") (pinfunction "C_C") (pintype "passive"))
      (node (ref "Q39") (pin "B") (pinfunction "B_B") (pintype "passive"))
      (node (ref "R65") (pin "2") (pinfunction "2_2") (pintype "passive"))
    )
    (net (code "62") (name "Net-(LED10-PadA)") (class "Default")
      (node (ref "LED10") (pin "A") (pinfunction "A_A") (pintype "passive"))
      (node (ref "Q40") (pin "B") (pinfunction "B_B") (pintype "passive"))
      (node (ref "R65") (pin "1") (pinfunction "1_1") (pintype "passive"))
    )
    (net (code "63") (name "Net-(LED10-PadC)") (class "Default")
      (node (ref "LED10") (pin "C") (pinfunction "C_C") (pintype "passive"))
      (node (ref "Q38") (pin "E") (pinfunction "E_E") (pintype "passive"))
      (node (ref "R64") (pin "2") (pinfunction "2_2") (pintype "passive"))
    )
    (net (code "64") (name "Net-(LED11-PadA)") (class "Default")
      (node (ref "LED11") (pin "A") (pinfunction "A_A") (pintype "passive"))
      (node (ref "Q62") (pin "E") (pinfunction "E_E") (pintype "passive"))
      (node (ref "R94") (pin "1") (pinfunction "1_1") (pintype "passive"))
    )
    (net (code "65") (name "Net-(LED11-PadC)") (class "Default")
      (node (ref "LED11") (pin "C") (pinfunction "C_C") (pintype "passive"))
      (node (ref "Q66") (pin "B") (pinfunction "B_B") (pintype "passive"))
      (node (ref "R97") (pin "2") (pinfunction "2_2") (pintype "passive"))
    )
    (net (code "66") (name "Net-(LED12-PadA)") (class "Default")
      (node (ref "LED12") (pin "A") (pinfunction "A_A") (pintype "passive"))
      (node (ref "Q67") (pin "B") (pinfunction "B_B") (pintype "passive"))
      (node (ref "R97") (pin "1") (pinfunction "1_1") (pintype "passive"))
    )
    (net (code "67") (name "Net-(LED12-PadC)") (class "Default")
      (node (ref "LED12") (pin "C") (pinfunction "C_C") (pintype "passive"))
      (node (ref "Q65") (pin "E") (pinfunction "E_E") (pintype "passive"))
      (node (ref "R96") (pin "2") (pinfunction "2_2") (pintype "passive"))
    )
    (net (code "68") (name "Net-(LED13-PadA)") (class "Default")
      (node (ref "LED13") (pin "A") (pinfunction "A_A") (pintype "passive"))
      (node (ref "Q79") (pin "B") (pinfunction "B_B") (pintype "passive"))
      (node (ref "R115") (pin "2") (pinfunction "2_2") (pintype "passive"))
    )
    (net (code "69") (name "Net-(LED14-PadC)") (class "Default")
      (node (ref "LED14") (pin "C") (pinfunction "C_C") (pintype "passive"))
      (node (ref "Q80") (pin "B") (pinfunction "B_B") (pintype "passive"))
      (node (ref "R116") (pin "1") (pinfunction "1_1") (pintype "passive"))
    )
    (net (code "70") (name "Net-(LED15-PadC)") (class "Default")
      (node (ref "LED15") (pin "C") (pinfunction "C_C") (pintype "passive"))
      (node (ref "Q81") (pin "E") (pinfunction "E_E") (pintype "passive"))
    )
    (net (code "71") (name "Net-(LED16-PadA)") (class "Default")
      (node (ref "LED16") (pin "A") (pinfunction "A_A") (pintype "passive"))
      (node (ref "Q82") (pin "E") (pinfunction "E_E") (pintype "passive"))
    )
    (net (code "72") (name "Net-(LED17-PadA)") (class "Default")
      (node (ref "LED17") (pin "A") (pinfunction "A_A") (pintype "passive"))
      (node (ref "R131") (pin "1") (pinfunction "1_1") (pintype "passive"))
    )
    (net (code "73") (name "Net-(LED18-PadC)") (class "Default")
      (node (ref "LED18") (pin "C") (pinfunction "C_C") (pintype "passive"))
      (node (ref "R132") (pin "2") (pinfunction "2_2") (pintype "passive"))
    )
    (net (code "74") (name "Net-(Q1A-D)") (class "Default")
      (node (ref "Q1") (pin "2") (pinfunction "D_2") (pintype "passive"))
      (node (ref "Q7") (pin "E") (pinfunction "E_E") (pintype "passive"))
      (node (ref "Q95") (pin "C") (pinfunction "C_C") (pintype "passive"))
    )
    (net (code "75") (name "Net-(Q1A-S)") (class "Default")
      (node (ref "Q1") (pin "3") (pinfunction "S_3") (pintype "passive"))
      (node (ref "R6") (pin "1") (pinfunction "1_1") (pintype "passive"))
    )
    (net (code "76") (name "Net-(Q1B-D)") (class "Default")
      (node (ref "Q1") (pin "5") (pinfunction "D_5") (pintype "passive"))
      (node (ref "Q6") (pin "E") (pinfunction "E_E") (pintype "passive"))
      (node (ref "Q96") (pin "C") (pinfunction "C_C") (pintype "passive"))
    )
    (net (code "77") (name "Net-(Q1B-S)") (class "Default")
      (node (ref "Q1") (pin "6") (pinfunction "S_6") (pintype "passive"))
      (node (ref "R8") (pin "1") (pinfunction "1_1") (pintype "passive"))
    )
    (net (code "78") (name "Net-(Q2-PadC)") (class "Default")
      (node (ref "Q2") (pin "C") (pinfunction "C_C") (pintype "passive"))
      (node (ref "R6") (pin "2") (pinfunction "2_2") (pintype "passive"))
      (node (ref "R8") (pin "2") (pinfunction "2_2") (pintype "passive"))
    )
    (net (code "79") (name "Net-(Q2-PadE)") (class "Default")
      (node (ref "Q2") (pin "E") (pinfunction "E_E") (pintype "passive"))
      (node (ref "R5") (pin "1") (pinfunction "1_1") (pintype "passive"))
    )
    (net (code "80") (name "Net-(Q3-PadC)") (class "Default")
      (node (ref "Q3") (pin "C") (pinfunction "C_C") (pintype "passive"))
      (node (ref "R10") (pin "1") (pinfunction "1_1") (pintype "passive"))
      (node (ref "R9") (pin "1") (pinfunction "1_1") (pintype "passive"))
    )
    (net (code "81") (name "Net-(Q3-PadE)") (class "Default")
      (node (ref "Q3") (pin "E") (pinfunction "E_E") (pintype "passive"))
      (node (ref "R7") (pin "2") (pinfunction "2_2") (pintype "passive"))
    )
    (net (code "82") (name "Net-(Q4A-D)") (class "Default")
      (node (ref "Q4") (pin "2") (pinfunction "D_2") (pintype "passive"))
      (node (ref "Q93") (pin "C") (pinfunction "C_C") (pintype "passive"))
      (node (ref "Q94") (pin "E") (pinfunction "E_E") (pintype "passive"))
    )
    (net (code "83") (name "Net-(Q4A-S)") (class "Default")
      (node (ref "Q4") (pin "3") (pinfunction "S_3") (pintype "passive"))
      (node (ref "R9") (pin "2") (pinfunction "2_2") (pintype "passive"))
    )
    (net (code "84") (name "Net-(Q4B-D)") (class "Default")
      (node (ref "Q4") (pin "5") (pinfunction "D_5") (pintype "passive"))
      (node (ref "Q5") (pin "C") (pinfunction "C_C") (pintype "passive"))
      (node (ref "Q8") (pin "E") (pinfunction "E_E") (pintype "passive"))
    )
    (net (code "85") (name "Net-(Q4B-S)") (class "Default")
      (node (ref "Q4") (pin "6") (pinfunction "S_6") (pintype "passive"))
      (node (ref "R10") (pin "2") (pinfunction "2_2") (pintype "passive"))
    )
    (net (code "86") (name "Net-(Q5-PadE)") (class "Default")
      (node (ref "Q5") (pin "E") (pinfunction "E_E") (pintype "passive"))
      (node (ref "R18") (pin "1") (pinfunction "1_1") (pintype "passive"))
    )
    (net (code "87") (name "Net-(Q6-PadB)") (class "Default")
      (node (ref "Q6") (pin "B") (pinfunction "B_B") (pintype "passive"))
      (node (ref "Q7") (pin "B") (pinfunction "B_B") (pintype "passive"))
      (node (ref "R16") (pin "1") (pinfunction "1_1") (pintype "passive"))
      (node (ref "R17") (pin "2") (pinfunction "2_2") (pintype "passive"))
    )
    (net (code "88") (name "Net-(Q8-PadB)") (class "Default")
      (node (ref "Q8") (pin "B") (pinfunction "B_B") (pintype "passive"))
      (node (ref "Q94") (pin "B") (pinfunction "B_B") (pintype "passive"))
      (node (ref "R14") (pin "1") (pinfunction "1_1") (pintype "passive"))
      (node (ref "R15") (pin "2") (pinfunction "2_2") (pintype "passive"))
    )
    (net (code "89") (name "Net-(Q9-PadE)") (class "Default")
      (node (ref "Q9") (pin "E") (pinfunction "E_E") (pintype "passive"))
      (node (ref "R25") (pin "1") (pinfunction "1_1") (pintype "passive"))
    )
    (net (code "90") (name "Net-(Q10-PadE)") (class "Default")
      (node (ref "Q10") (pin "E") (pinfunction "E_E") (pintype "passive"))
      (node (ref "R24") (pin "2") (pinfunction "2_2") (pintype "passive"))
    )
    (net (code "91") (name "Net-(Q11-PadC)") (class "Default")
      (node (ref "Q11") (pin "C") (pinfunction "C_C") (pintype "passive"))
      (node (ref "R24") (pin "1") (pinfunction "1_1") (pintype "passive"))
      (node (ref "R27") (pin "2") (pinfunction "2_2") (pintype "passive"))
      (node (ref "R32") (pin "2") (pinfunction "2_2") (pintype "passive"))
    )
    (net (code "92") (name "Net-(Q11-PadE)") (class "Default")
      (node (ref "Q11") (pin "E") (pinfunction "E_E") (pintype "passive"))
      (node (ref "R23") (pin "1") (pinfunction "1_1") (pintype "passive"))
    )
    (net (code "93") (name "Net-(Q12-PadC)") (class "Default")
      (node (ref "Q12") (pin "C") (pinfunction "C_C") (pintype "passive"))
      (node (ref "R25") (pin "2") (pinfunction "2_2") (pintype "passive"))
      (node (ref "R28") (pin "1") (pinfunction "1_1") (pintype "passive"))
      (node (ref "R33") (pin "1") (pinfunction "1_1") (pintype "passive"))
    )
    (net (code "94") (name "Net-(Q12-PadE)") (class "Default")
      (node (ref "Q12") (pin "E") (pinfunction "E_E") (pintype "passive"))
      (node (ref "R26") (pin "2") (pinfunction "2_2") (pintype "passive"))
    )
    (net (code "95") (name "Net-(Q13-PadB)") (class "Default")
      (node (ref "Q13") (pin "B") (pinfunction "B_B") (pintype "passive"))
      (node (ref "R27") (pin "1") (pinfunction "1_1") (pintype "passive"))
    )
    (net (code "96") (name "Net-(Q13-PadE)") (class "Default")
      (node (ref "Q13") (pin "E") (pinfunction "E_E") (pintype "passive"))
      (node (ref "R30") (pin "2") (pinfunction "2_2") (pintype "passive"))
    )
    (net (code "97") (name "Net-(Q14-PadB)") (class "Default")
      (node (ref "Q14") (pin "B") (pinfunction "B_B") (pintype "passive"))
      (node (ref "R28") (pin "2") (pinfunction "2_2") (pintype "passive"))
    )
    (net (code "98") (name "Net-(Q14-PadE)") (class "Default")
      (node (ref "Q14") (pin "E") (pinfunction "E_E") (pintype "passive"))
      (node (ref "R31") (pin "1") (pinfunction "1_1") (pintype "passive"))
    )
    (net (code "99") (name "Net-(Q15-PadB)") (class "Default")
      (node (ref "Q15") (pin "B") (pinfunction "B_B") (pintype "passive"))
      (node (ref "R32") (pin "1") (pinfunction "1_1") (pintype "passive"))
    )
    (net (code "100") (name "Net-(Q15-PadE)") (class "Default")
      (node (ref "Q15") (pin "E") (pinfunction "E_E") (pintype "passive"))
      (node (ref "R34") (pin "2") (pinfunction "2_2") (pintype "passive"))
    )
    (net (code "101") (name "Net-(Q16-PadB)") (class "Default")
      (node (ref "Q16") (pin "B") (pinfunction "B_B") (pintype "passive"))
      (node (ref "R33") (pin "2") (pinfunction "2_2") (pintype "passive"))
    )
    (net (code "102") (name "Net-(Q16-PadE)") (class "Default")
      (node (ref "Q16") (pin "E") (pinfunction "E_E") (pintype "passive"))
      (node (ref "R35") (pin "1") (pinfunction "1_1") (pintype "passive"))
    )
    (net (code "103") (name "Net-(Q17-PadE)") (class "Default")
      (node (ref "Q17") (pin "E") (pinfunction "E_E") (pintype "passive"))
      (node (ref "R40") (pin "1") (pinfunction "1_1") (pintype "passive"))
    )
    (net (code "104") (name "Net-(Q18-PadE)") (class "Default")
      (node (ref "Q18") (pin "E") (pinfunction "E_E") (pintype "passive"))
      (node (ref "R39") (pin "2") (pinfunction "2_2") (pintype "passive"))
    )
    (net (code "105") (name "Net-(Q19-PadC)") (class "Default")
      (node (ref "Q19") (pin "C") (pinfunction "C_C") (pintype "passive"))
      (node (ref "R39") (pin "1") (pinfunction "1_1") (pintype "passive"))
      (node (ref "R42") (pin "2") (pinfunction "2_2") (pintype "passive"))
      (node (ref "R47") (pin "2") (pinfunction "2_2") (pintype "passive"))
    )
    (net (code "106") (name "Net-(Q19-PadE)") (class "Default")
      (node (ref "Q19") (pin "E") (pinfunction "E_E") (pintype "passive"))
      (node (ref "R38") (pin "1") (pinfunction "1_1") (pintype "passive"))
    )
    (net (code "107") (name "Net-(Q20-PadC)") (class "Default")
      (node (ref "Q20") (pin "C") (pinfunction "C_C") (pintype "passive"))
      (node (ref "R40") (pin "2") (pinfunction "2_2") (pintype "passive"))
      (node (ref "R43") (pin "1") (pinfunction "1_1") (pintype "passive"))
      (node (ref "R48") (pin "1") (pinfunction "1_1") (pintype "passive"))
    )
    (net (code "108") (name "Net-(Q20-PadE)") (class "Default")
      (node (ref "Q20") (pin "E") (pinfunction "E_E") (pintype "passive"))
      (node (ref "R41") (pin "2") (pinfunction "2_2") (pintype "passive"))
    )
    (net (code "109") (name "Net-(Q21-PadB)") (class "Default")
      (node (ref "Q21") (pin "B") (pinfunction "B_B") (pintype "passive"))
      (node (ref "R42") (pin "1") (pinfunction "1_1") (pintype "passive"))
    )
    (net (code "110") (name "Net-(Q21-PadE)") (class "Default")
      (node (ref "Q21") (pin "E") (pinfunction "E_E") (pintype "passive"))
      (node (ref "R45") (pin "2") (pinfunction "2_2") (pintype "passive"))
    )
    (net (code "111") (name "Net-(Q22-PadB)") (class "Default")
      (node (ref "Q22") (pin "B") (pinfunction "B_B") (pintype "passive"))
      (node (ref "R43") (pin "2") (pinfunction "2_2") (pintype "passive"))
    )
    (net (code "112") (name "Net-(Q22-PadE)") (class "Default")
      (node (ref "Q22") (pin "E") (pinfunction "E_E") (pintype "passive"))
      (node (ref "R46") (pin "1") (pinfunction "1_1") (pintype "passive"))
    )
    (net (code "113") (name "Net-(Q23-PadB)") (class "Default")
      (node (ref "Q23") (pin "B") (pinfunction "B_B") (pintype "passive"))
      (node (ref "R47") (pin "1") (pinfunction "1_1") (pintype "passive"))
    )
    (net (code "114") (name "Net-(Q23-PadE)") (class "Default")
      (node (ref "Q23") (pin "E") (pinfunction "E_E") (pintype "passive"))
      (node (ref "R49") (pin "2") (pinfunction "2_2") (pintype "passive"))
    )
    (net (code "115") (name "Net-(Q24-PadB)") (class "Default")
      (node (ref "Q24") (pin "B") (pinfunction "B_B") (pintype "passive"))
      (node (ref "R48") (pin "2") (pinfunction "2_2") (pintype "passive"))
    )
    (net (code "116") (name "Net-(Q24-PadE)") (class "Default")
      (node (ref "Q24") (pin "E") (pinfunction "E_E") (pintype "passive"))
      (node (ref "R50") (pin "1") (pinfunction "1_1") (pintype "passive"))
    )
    (net (code "117") (name "Net-(Q25-PadE)") (class "Default")
      (node (ref "Q25") (pin "E") (pinfunction "E_E") (pintype "passive"))
      (node (ref "R54") (pin "1") (pinfunction "1_1") (pintype "passive"))
    )
    (net (code "118") (name "Net-(Q26-PadC)") (class "Default")
      (node (ref "Q26") (pin "C") (pinfunction "C_C") (pintype "passive"))
      (node (ref "Q31") (pin "E") (pinfunction "E_E") (pintype "passive"))
      (node (ref "R60") (pin "1") (pinfunction "1_1") (pintype "passive"))
    )
    (net (code "119") (name "Net-(Q26-PadE)") (class "Default")
      (node (ref "Q26") (pin "E") (pinfunction "E_E") (pintype "passive"))
      (node (ref "R55") (pin "1") (pinfunction "1_1") (pintype "passive"))
    )
    (net (code "120") (name "Net-(Q27-PadC)") (class "Default")
      (node (ref "Q27") (pin "C") (pinfunction "C_C") (pintype "passive"))
      (node (ref "Q30") (pin "E") (pinfunction "E_E") (pintype "passive"))
      (node (ref "R59") (pin "2") (pinfunction "2_2") (pintype "passive"))
    )
    (net (code "121") (name "Net-(Q27-PadE)") (class "Default")
      (node (ref "Q27") (pin "E") (pinfunction "E_E") (pintype "passive"))
      (node (ref "R56") (pin "2") (pinfunction "2_2") (pintype "passive"))
    )
    (net (code "122") (name "Net-(Q28-PadE)") (class "Default")
      (node (ref "Q28") (pin "E") (pinfunction "E_E") (pintype "passive"))
      (node (ref "R57") (pin "2") (pinfunction "2_2") (pintype "passive"))
    )
    (net (code "123") (name "Net-(Q29-PadC)") (class "Default")
      (node (ref "Q29") (pin "C") (pinfunction "C_C") (pintype "passive"))
      (node (ref "Q33") (pin "C") (pinfunction "C_C") (pintype "passive"))
      (node (ref "Q36") (pin "B") (pinfunction "B_B") (pintype "passive"))
    )
    (net (code "124") (name "Net-(Q29-PadE)") (class "Default")
      (node (ref "Q29") (pin "E") (pinfunction "E_E") (pintype "passive"))
      (node (ref "Q30") (pin "C") (pinfunction "C_C") (pintype "passive"))
    )
    (net (code "125") (name "Net-(Q31-PadC)") (class "Default")
      (node (ref "Q31") (pin "C") (pinfunction "C_C") (pintype "passive"))
      (node (ref "Q32") (pin "E") (pinfunction "E_E") (pintype "passive"))
    )
    (net (code "126") (name "Net-(Q32-PadC)") (class "Default")
      (node (ref "Q32") (pin "C") (pinfunction "C_C") (pintype "passive"))
      (node (ref "Q34") (pin "C") (pinfunction "C_C") (pintype "passive"))
      (node (ref "Q37") (pin "B") (pinfunction "B_B") (pintype "passive"))
    )
    (net (code "127") (name "Net-(Q33-PadB)") (class "Default")
      (node (ref "Q33") (pin "B") (pinfunction "B_B") (pintype "passive"))
      (node (ref "Q35") (pin "B") (pinfunction "B_B") (pintype "passive"))
      (node (ref "Q35") (pin "C") (pinfunction "C_C") (pintype "passive"))
      (node (ref "Q36") (pin "E") (pinfunction "E_E") (pintype "passive"))
    )
    (net (code "128") (name "Net-(Q33-PadE)") (class "Default")
      (node (ref "Q33") (pin "E") (pinfunction "E_E") (pintype "passive"))
      (node (ref "R58") (pin "1") (pinfunction "1_1") (pintype "passive"))
    )
    (net (code "129") (name "Net-(Q34-PadB)") (class "Default")
      (node (ref "Q34") (pin "B") (pinfunction "B_B") (pintype "passive"))
      (node (ref "Q37") (pin "E") (pinfunction "E_E") (pintype "passive"))
      (node (ref "Q38") (pin "B") (pinfunction "B_B") (pintype "passive"))
      (node (ref "Q38") (pin "C") (pinfunction "C_C") (pintype "passive"))
    )
    (net (code "130") (name "Net-(Q34-PadE)") (class "Default")
      (node (ref "Q34") (pin "E") (pinfunction "E_E") (pintype "passive"))
      (node (ref "R61") (pin "2") (pinfunction "2_2") (pintype "passive"))
    )
    (net (code "131") (name "Net-(Q36-PadC)") (class "Default")
      (node (ref "Q36") (pin "C") (pinfunction "C_C") (pintype "passive"))
      (node (ref "Q39") (pin "E") (pinfunction "E_E") (pintype "passive"))
    )
    (net (code "132") (name "Net-(Q37-PadC)") (class "Default")
      (node (ref "Q37") (pin "C") (pinfunction "C_C") (pintype "passive"))
      (node (ref "Q40") (pin "E") (pinfunction "E_E") (pintype "passive"))
    )
    (net (code "133") (name "Net-(Q41-PadB)") (class "Default")
      (node (ref "Q41") (pin "B") (pinfunction "B_B") (pintype "passive"))
      (node (ref "Q41") (pin "C") (pinfunction "C_C") (pintype "passive"))
      (node (ref "Q43") (pin "B") (pinfunction "B_B") (pintype "passive"))
      (node (ref "R68") (pin "2") (pinfunction "2_2") (pintype "passive"))
    )
    (net (code "134") (name "Net-(Q41-PadE)") (class "Default")
      (node (ref "Q41") (pin "E") (pinfunction "E_E") (pintype "passive"))
      (node (ref "R67") (pin "1") (pinfunction "1_1") (pintype "passive"))
    )
    (net (code "135") (name "Net-(Q42-PadB)") (class "Default")
      (node (ref "Q42") (pin "B") (pinfunction "B_B") (pintype "passive"))
      (node (ref "Q42") (pin "C") (pinfunction "C_C") (pintype "passive"))
      (node (ref "Q44") (pin "B") (pinfunction "B_B") (pintype "passive"))
      (node (ref "R69") (pin "1") (pinfunction "1_1") (pintype "passive"))
    )
    (net (code "136") (name "Net-(Q42-PadE)") (class "Default")
      (node (ref "Q42") (pin "E") (pinfunction "E_E") (pintype "passive"))
      (node (ref "R70") (pin "2") (pinfunction "2_2") (pintype "passive"))
    )
    (net (code "137") (name "Net-(Q43-PadE)") (class "Default")
      (node (ref "Q43") (pin "E") (pinfunction "E_E") (pintype "passive"))
      (node (ref "R71") (pin "1") (pinfunction "1_1") (pintype "passive"))
    )
    (net (code "138") (name "Net-(Q44-PadE)") (class "Default")
      (node (ref "Q44") (pin "E") (pinfunction "E_E") (pintype "passive"))
      (node (ref "R72") (pin "2") (pinfunction "2_2") (pintype "passive"))
    )
    (net (code "139") (name "Net-(Q46-PadE)") (class "Default")
      (node (ref "Q46") (pin "E") (pinfunction "E_E") (pintype "passive"))
      (node (ref "Q48") (pin "B") (pinfunction "B_B") (pintype "passive"))
      (node (ref "R77") (pin "2") (pinfunction "2_2") (pintype "passive"))
    )
    (net (code "140") (name "Net-(Q47-PadE)") (class "Default")
      (node (ref "Q47") (pin "E") (pinfunction "E_E") (pintype "passive"))
      (node (ref "Q49") (pin "B") (pinfunction "B_B") (pintype "passive"))
      (node (ref "R77") (pin "1") (pinfunction "1_1") (pintype "passive"))
    )
    (net (code "141") (name "Net-(Q48-PadE)") (class "Default")
      (node (ref "Q48") (pin "E") (pinfunction "E_E") (pintype "passive"))
      (node (ref "Q50") (pin "B") (pinfunction "B_B") (pintype "passive"))
      (node (ref "R78") (pin "2") (pinfunction "2_2") (pintype "passive"))
    )
    (net (code "142") (name "Net-(Q49-PadE)") (class "Default")
      (node (ref "Q49") (pin "E") (pinfunction "E_E") (pintype "passive"))
      (node (ref "Q51") (pin "B") (pinfunction "B_B") (pintype "passive"))
      (node (ref "R78") (pin "1") (pinfunction "1_1") (pintype "passive"))
    )
    (net (code "143") (name "Net-(Q50-PadE)") (class "Default")
      (node (ref "Q50") (pin "E") (pinfunction "E_E") (pintype "passive"))
      (node (ref "R80") (pin "2") (pinfunction "2_2") (pintype "passive"))
    )
    (net (code "144") (name "Net-(Q51-PadE)") (class "Default")
      (node (ref "Q51") (pin "E") (pinfunction "E_E") (pintype "passive"))
      (node (ref "R81") (pin "1") (pinfunction "1_1") (pintype "passive"))
    )
    (net (code "145") (name "Net-(Q52-PadE)") (class "Default")
      (node (ref "Q52") (pin "E") (pinfunction "E_E") (pintype "passive"))
      (node (ref "R86") (pin "1") (pinfunction "1_1") (pintype "passive"))
    )
    (net (code "146") (name "Net-(Q53-PadC)") (class "Default")
      (node (ref "Q53") (pin "C") (pinfunction "C_C") (pintype "passive"))
      (node (ref "Q58") (pin "E") (pinfunction "E_E") (pintype "passive"))
      (node (ref "R92") (pin "1") (pinfunction "1_1") (pintype "passive"))
    )
    (net (code "147") (name "Net-(Q53-PadE)") (class "Default")
      (node (ref "Q53") (pin "E") (pinfunction "E_E") (pintype "passive"))
      (node (ref "R87") (pin "1") (pinfunction "1_1") (pintype "passive"))
    )
    (net (code "148") (name "Net-(Q54-PadC)") (class "Default")
      (node (ref "Q54") (pin "C") (pinfunction "C_C") (pintype "passive"))
      (node (ref "Q57") (pin "E") (pinfunction "E_E") (pintype "passive"))
      (node (ref "R91") (pin "2") (pinfunction "2_2") (pintype "passive"))
    )
    (net (code "149") (name "Net-(Q54-PadE)") (class "Default")
      (node (ref "Q54") (pin "E") (pinfunction "E_E") (pintype "passive"))
      (node (ref "R88") (pin "2") (pinfunction "2_2") (pintype "passive"))
    )
    (net (code "150") (name "Net-(Q55-PadE)") (class "Default")
      (node (ref "Q55") (pin "E") (pinfunction "E_E") (pintype "passive"))
      (node (ref "R89") (pin "2") (pinfunction "2_2") (pintype "passive"))
    )
    (net (code "151") (name "Net-(Q56-PadC)") (class "Default")
      (node (ref "Q56") (pin "C") (pinfunction "C_C") (pintype "passive"))
      (node (ref "Q60") (pin "C") (pinfunction "C_C") (pintype "passive"))
      (node (ref "Q63") (pin "B") (pinfunction "B_B") (pintype "passive"))
    )
    (net (code "152") (name "Net-(Q56-PadE)") (class "Default")
      (node (ref "Q56") (pin "E") (pinfunction "E_E") (pintype "passive"))
      (node (ref "Q57") (pin "C") (pinfunction "C_C") (pintype "passive"))
    )
    (net (code "153") (name "Net-(Q58-PadC)") (class "Default")
      (node (ref "Q58") (pin "C") (pinfunction "C_C") (pintype "passive"))
      (node (ref "Q59") (pin "E") (pinfunction "E_E") (pintype "passive"))
    )
    (net (code "154") (name "Net-(Q59-PadC)") (class "Default")
      (node (ref "Q59") (pin "C") (pinfunction "C_C") (pintype "passive"))
      (node (ref "Q61") (pin "C") (pinfunction "C_C") (pintype "passive"))
      (node (ref "Q64") (pin "B") (pinfunction "B_B") (pintype "passive"))
    )
    (net (code "155") (name "Net-(Q60-PadB)") (class "Default")
      (node (ref "Q60") (pin "B") (pinfunction "B_B") (pintype "passive"))
      (node (ref "Q62") (pin "B") (pinfunction "B_B") (pintype "passive"))
      (node (ref "Q62") (pin "C") (pinfunction "C_C") (pintype "passive"))
      (node (ref "Q63") (pin "E") (pinfunction "E_E") (pintype "passive"))
    )
    (net (code "156") (name "Net-(Q60-PadE)") (class "Default")
      (node (ref "Q60") (pin "E") (pinfunction "E_E") (pintype "passive"))
      (node (ref "R90") (pin "1") (pinfunction "1_1") (pintype "passive"))
    )
    (net (code "157") (name "Net-(Q61-PadB)") (class "Default")
      (node (ref "Q61") (pin "B") (pinfunction "B_B") (pintype "passive"))
      (node (ref "Q64") (pin "E") (pinfunction "E_E") (pintype "passive"))
      (node (ref "Q65") (pin "B") (pinfunction "B_B") (pintype "passive"))
      (node (ref "Q65") (pin "C") (pinfunction "C_C") (pintype "passive"))
    )
    (net (code "158") (name "Net-(Q61-PadE)") (class "Default")
      (node (ref "Q61") (pin "E") (pinfunction "E_E") (pintype "passive"))
      (node (ref "R93") (pin "2") (pinfunction "2_2") (pintype "passive"))
    )
    (net (code "159") (name "Net-(Q63-PadC)") (class "Default")
      (node (ref "Q63") (pin "C") (pinfunction "C_C") (pintype "passive"))
      (node (ref "Q66") (pin "E") (pinfunction "E_E") (pintype "passive"))
    )
    (net (code "160") (name "Net-(Q64-PadC)") (class "Default")
      (node (ref "Q64") (pin "C") (pinfunction "C_C") (pintype "passive"))
      (node (ref "Q67") (pin "E") (pinfunction "E_E") (pintype "passive"))
    )
    (net (code "161") (name "Net-(Q68-PadB)") (class "Default")
      (node (ref "Q68") (pin "B") (pinfunction "B_B") (pintype "passive"))
      (node (ref "Q68") (pin "C") (pinfunction "C_C") (pintype "passive"))
      (node (ref "Q70") (pin "B") (pinfunction "B_B") (pintype "passive"))
      (node (ref "R100") (pin "2") (pinfunction "2_2") (pintype "passive"))
    )
    (net (code "162") (name "Net-(Q68-PadE)") (class "Default")
      (node (ref "Q68") (pin "E") (pinfunction "E_E") (pintype "passive"))
      (node (ref "R99") (pin "1") (pinfunction "1_1") (pintype "passive"))
    )
    (net (code "163") (name "Net-(Q69-PadB)") (class "Default")
      (node (ref "Q69") (pin "B") (pinfunction "B_B") (pintype "passive"))
      (node (ref "Q69") (pin "C") (pinfunction "C_C") (pintype "passive"))
      (node (ref "Q71") (pin "B") (pinfunction "B_B") (pintype "passive"))
      (node (ref "R101") (pin "1") (pinfunction "1_1") (pintype "passive"))
    )
    (net (code "164") (name "Net-(Q69-PadE)") (class "Default")
      (node (ref "Q69") (pin "E") (pinfunction "E_E") (pintype "passive"))
      (node (ref "R102") (pin "2") (pinfunction "2_2") (pintype "passive"))
    )
    (net (code "165") (name "Net-(Q70-PadE)") (class "Default")
      (node (ref "Q70") (pin "E") (pinfunction "E_E") (pintype "passive"))
      (node (ref "R103") (pin "1") (pinfunction "1_1") (pintype "passive"))
    )
    (net (code "166") (name "Net-(Q71-PadE)") (class "Default")
      (node (ref "Q71") (pin "E") (pinfunction "E_E") (pintype "passive"))
      (node (ref "R104") (pin "2") (pinfunction "2_2") (pintype "passive"))
    )
    (net (code "167") (name "Net-(Q73-PadE)") (class "Default")
      (node (ref "Q73") (pin "E") (pinfunction "E_E") (pintype "passive"))
      (node (ref "Q75") (pin "B") (pinfunction "B_B") (pintype "passive"))
      (node (ref "R109") (pin "2") (pinfunction "2_2") (pintype "passive"))
    )
    (net (code "168") (name "Net-(Q74-PadE)") (class "Default")
      (node (ref "Q74") (pin "E") (pinfunction "E_E") (pintype "passive"))
      (node (ref "Q76") (pin "B") (pinfunction "B_B") (pintype "passive"))
      (node (ref "R109") (pin "1") (pinfunction "1_1") (pintype "passive"))
    )
    (net (code "169") (name "Net-(Q75-PadE)") (class "Default")
      (node (ref "Q75") (pin "E") (pinfunction "E_E") (pintype "passive"))
      (node (ref "Q77") (pin "B") (pinfunction "B_B") (pintype "passive"))
      (node (ref "R110") (pin "2") (pinfunction "2_2") (pintype "passive"))
    )
    (net (code "170") (name "Net-(Q76-PadE)") (class "Default")
      (node (ref "Q76") (pin "E") (pinfunction "E_E") (pintype "passive"))
      (node (ref "Q78") (pin "B") (pinfunction "B_B") (pintype "passive"))
      (node (ref "R110") (pin "1") (pinfunction "1_1") (pintype "passive"))
    )
    (net (code "171") (name "Net-(Q77-PadE)") (class "Default")
      (node (ref "Q77") (pin "E") (pinfunction "E_E") (pintype "passive"))
      (node (ref "R112") (pin "2") (pinfunction "2_2") (pintype "passive"))
    )
    (net (code "172") (name "Net-(Q78-PadE)") (class "Default")
      (node (ref "Q78") (pin "E") (pinfunction "E_E") (pintype "passive"))
      (node (ref "R113") (pin "1") (pinfunction "1_1") (pintype "passive"))
    )
    (net (code "173") (name "Net-(Q79-PadC)") (class "Default")
      (node (ref "Q79") (pin "C") (pinfunction "C_C") (pintype "passive"))
      (node (ref "Q81") (pin "B") (pinfunction "B_B") (pintype "passive"))
      (node (ref "Q81") (pin "C") (pinfunction "C_C") (pintype "passive"))
      (node (ref "Q83") (pin "B") (pinfunction "B_B") (pintype "passive"))
    )
    (net (code "174") (name "Net-(Q79-PadE)") (class "Default")
      (node (ref "Q79") (pin "E") (pinfunction "E_E") (pintype "passive"))
      (node (ref "R117") (pin "1") (pinfunction "1_1") (pintype "passive"))
    )
    (net (code "175") (name "Net-(Q80-PadC)") (class "Default")
      (node (ref "Q80") (pin "C") (pinfunction "C_C") (pintype "passive"))
      (node (ref "Q82") (pin "B") (pinfunction "B_B") (pintype "passive"))
      (node (ref "Q82") (pin "C") (pinfunction "C_C") (pintype "passive"))
      (node (ref "Q84") (pin "B") (pinfunction "B_B") (pintype "passive"))
    )
    (net (code "176") (name "Net-(Q80-PadE)") (class "Default")
      (node (ref "Q80") (pin "E") (pinfunction "E_E") (pintype "passive"))
      (node (ref "R118") (pin "2") (pinfunction "2_2") (pintype "passive"))
    )
    (net (code "177") (name "Net-(Q83-PadE)") (class "Default")
      (node (ref "Q83") (pin "E") (pinfunction "E_E") (pintype "passive"))
      (node (ref "R119") (pin "2") (pinfunction "2_2") (pintype "passive"))
    )
    (net (code "178") (name "Net-(Q84-PadE)") (class "Default")
      (node (ref "Q84") (pin "E") (pinfunction "E_E") (pintype "passive"))
      (node (ref "R122") (pin "1") (pinfunction "1_1") (pintype "passive"))
    )
    (net (code "179") (name "Net-(Q85-PadB)") (class "Default")
      (node (ref "Q85") (pin "B") (pinfunction "B_B") (pintype "passive"))
      (node (ref "R123") (pin "2") (pinfunction "2_2") (pintype "passive"))
    )
    (net (code "180") (name "Net-(Q85-PadE)") (class "Default")
      (node (ref "Q85") (pin "E") (pinfunction "E_E") (pintype "passive"))
      (node (ref "R120") (pin "2") (pinfunction "2_2") (pintype "passive"))
    )
    (net (code "181") (name "Net-(Q86-PadB)") (class "Default")
      (node (ref "Q86") (pin "B") (pinfunction "B_B") (pintype "passive"))
      (node (ref "R124") (pin "2") (pinfunction "2_2") (pintype "passive"))
    )
    (net (code "182") (name "Net-(Q86-PadE)") (class "Default")
      (node (ref "Q86") (pin "E") (pinfunction "E_E") (pintype "passive"))
      (node (ref "R121") (pin "1") (pinfunction "1_1") (pintype "passive"))
    )
    (net (code "183") (name "Net-(Q87-PadE)") (class "Default")
      (node (ref "Q87") (pin "E") (pinfunction "E_E") (pintype "passive"))
      (node (ref "Q89") (pin "B") (pinfunction "B_B") (pintype "passive"))
    )
    (net (code "184") (name "Net-(Q88-PadE)") (class "Default")
      (node (ref "Q88") (pin "E") (pinfunction "E_E") (pintype "passive"))
      (node (ref "Q90") (pin "B") (pinfunction "B_B") (pintype "passive"))
    )
    (net (code "185") (name "Net-(Q91-PadS)") (class "Default")
      (node (ref "Q91") (pin "S") (pinfunction "S_S") (pintype "passive"))
      (node (ref "R125") (pin "2") (pinfunction "2_2") (pintype "passive"))
    )
    (net (code "186") (name "Net-(Q92-PadS)") (class "Default")
      (node (ref "Q92") (pin "S") (pinfunction "S_S") (pintype "passive"))
      (node (ref "R126") (pin "2") (pinfunction "2_2") (pintype "passive"))
    )
    (net (code "187") (name "Net-(Q93-PadE)") (class "Default")
      (node (ref "Q93") (pin "E") (pinfunction "E_E") (pintype "passive"))
      (node (ref "R12") (pin "1") (pinfunction "1_1") (pintype "passive"))
    )
    (net (code "188") (name "Net-(Q95-PadE)") (class "Default")
      (node (ref "Q95") (pin "E") (pinfunction "E_E") (pintype "passive"))
      (node (ref "R13") (pin "2") (pinfunction "2_2") (pintype "passive"))
    )
    (net (code "189") (name "Net-(Q96-PadE)") (class "Default")
      (node (ref "Q96") (pin "E") (pinfunction "E_E") (pintype "passive"))
      (node (ref "R19") (pin "2") (pinfunction "2_2") (pintype "passive"))
    )
    (net (code "190") (name "Net-(R1-S)") (class "Default")
      (node (ref "R1") (pin "2") (pinfunction "S_2") (pintype "passive"))
      (node (ref "R2") (pin "2") (pinfunction "2_2") (pintype "passive"))
    )
    (net (code "191") (name "Net-(R2-Pad1)") (class "Default")
      (node (ref "R2") (pin "1") (pinfunction "1_1") (pintype "passive"))
      (node (ref "R3") (pin "1") (pinfunction "1_1") (pintype "passive"))
      (node (ref "R4") (pin "2") (pinfunction "2_2") (pintype "passive"))
    )
    (net (code "192") (name "Net-(R59-Pad1)") (class "Default")
      (node (ref "R59") (pin "1") (pinfunction "1_1") (pintype "passive"))
      (node (ref "R60") (pin "2") (pinfunction "2_2") (pintype "passive"))
      (node (ref "R63") (pin "2") (pinfunction "2_2") (pintype "passive"))
      (node (ref "R66") (pin "1") (pinfunction "1_1") (pintype "passive"))
    )
    (net (code "193") (name "Net-(R74-A)") (class "Default")
      (node (ref "C18") (pin "2") (pinfunction "2_2") (pintype "passive"))
      (node (ref "C20") (pin "1") (pinfunction "1_1") (pintype "passive"))
      (node (ref "Q40") (pin "C") (pinfunction "C_C") (pintype "passive"))
      (node (ref "Q44") (pin "C") (pinfunction "C_C") (pintype "passive"))
      (node (ref "Q45") (pin "E") (pinfunction "E_E") (pintype "passive"))
      (node (ref "Q47") (pin "B") (pinfunction "B_B") (pintype "passive"))
      (node (ref "R74") (pin "1") (pinfunction "A_1") (pintype "passive"))
      (node (ref "R74") (pin "2") (pinfunction "S_2") (pintype "passive"))
      (node (ref "R76") (pin "2") (pinfunction "2_2") (pintype "passive"))
    )
    (net (code "194") (name "Net-(R74-E)") (class "Default")
      (node (ref "Q45") (pin "B") (pinfunction "B_B") (pintype "passive"))
      (node (ref "R73") (pin "1") (pinfunction "1_1") (pintype "passive"))
      (node (ref "R74") (pin "3") (pinfunction "E_3") (pintype "passive"))
    )
    (net (code "195") (name "Net-(R91-Pad1)") (class "Default")
      (node (ref "R91") (pin "1") (pinfunction "1_1") (pintype "passive"))
      (node (ref "R92") (pin "2") (pinfunction "2_2") (pintype "passive"))
      (node (ref "R95") (pin "2") (pinfunction "2_2") (pintype "passive"))
      (node (ref "R98") (pin "1") (pinfunction "1_1") (pintype "passive"))
    )
    (net (code "196") (name "Net-(R106-A)") (class "Default")
      (node (ref "C28") (pin "2") (pinfunction "2_2") (pintype "passive"))
      (node (ref "C30") (pin "1") (pinfunction "1_1") (pintype "passive"))
      (node (ref "Q67") (pin "C") (pinfunction "C_C") (pintype "passive"))
      (node (ref "Q71") (pin "C") (pinfunction "C_C") (pintype "passive"))
      (node (ref "Q72") (pin "E") (pinfunction "E_E") (pintype "passive"))
      (node (ref "Q74") (pin "B") (pinfunction "B_B") (pintype "passive"))
      (node (ref "R106") (pin "1") (pinfunction "A_1") (pintype "passive"))
      (node (ref "R106") (pin "2") (pinfunction "S_2") (pintype "passive"))
      (node (ref "R108") (pin "2") (pinfunction "2_2") (pintype "passive"))
    )
    (net (code "197") (name "Net-(R106-E)") (class "Default")
      (node (ref "Q72") (pin "B") (pinfunction "B_B") (pintype "passive"))
      (node (ref "R105") (pin "1") (pinfunction "1_1") (pintype "passive"))
      (node (ref "R106") (pin "3") (pinfunction "E_3") (pintype "passive"))
    )
    (net (code "198") (name "OUT+") (class "Default")
      (node (ref "PAD1") (pin "P$1") (pinfunction "P$1_P$1") (pintype "bidirectional"))
      (node (ref "R66") (pin "2") (pinfunction "2_2") (pintype "passive"))
      (node (ref "R80") (pin "1") (pinfunction "1_1") (pintype "passive"))
      (node (ref "R81") (pin "2") (pinfunction "2_2") (pintype "passive"))
      (node (ref "R82") (pin "1") (pinfunction "1_1") (pintype "passive"))
    )
    (net (code "199") (name "OUT-") (class "Default")
      (node (ref "PAD2") (pin "P$1") (pinfunction "P$1_P$1") (pintype "bidirectional"))
      (node (ref "R112") (pin "1") (pinfunction "1_1") (pintype "passive"))
      (node (ref "R113") (pin "2") (pinfunction "2_2") (pintype "passive"))
      (node (ref "R114") (pin "1") (pinfunction "1_1") (pintype "passive"))
      (node (ref "R98") (pin "2") (pinfunction "2_2") (pintype "passive"))
    )
    (net (code "200") (name "UOUT+") (class "Default")
      (node (ref "Q10") (pin "B") (pinfunction "B_B") (pintype "passive"))
      (node (ref "Q7") (pin "C") (pinfunction "C_C") (pintype "passive"))
      (node (ref "Q9") (pin "B") (pinfunction "B_B") (pintype "passive"))
      (node (ref "Q94") (pin "C") (pinfunction "C_C") (pintype "passive"))
      (node (ref "R11") (pin "2") (pinfunction "2_2") (pintype "passive"))
      (node (ref "R21") (pin "2") (pinfunction "2_2") (pintype "passive"))
    )
    (net (code "201") (name "UOUT-") (class "Default")
      (node (ref "Q17") (pin "B") (pinfunction "B_B") (pintype "passive"))
      (node (ref "Q18") (pin "B") (pinfunction "B_B") (pintype "passive"))
      (node (ref "Q6") (pin "C") (pinfunction "C_C") (pintype "passive"))
      (node (ref "Q8") (pin "C") (pinfunction "C_C") (pintype "passive"))
      (node (ref "R20") (pin "2") (pinfunction "2_2") (pintype "passive"))
      (node (ref "R36") (pin "2") (pinfunction "2_2") (pintype "passive"))
    )
    (net (code "202") (name "V+") (class "Default")
      (node (ref "C1") (pin "+") (pinfunction "+_+") (pintype "passive"))
      (node (ref "C11") (pin "1") (pinfunction "1_1") (pintype "passive"))
      (node (ref "C14") (pin "2") (pinfunction "2_2") (pintype "passive"))
      (node (ref "C23") (pin "1") (pinfunction "1_1") (pintype "passive"))
      (node (ref "C25") (pin "+") (pinfunction "+_+") (pintype "passive"))
      (node (ref "C3") (pin "2") (pinfunction "2_2") (pintype "passive"))
      (node (ref "C33") (pin "1") (pinfunction "1_1") (pintype "passive"))
      (node (ref "C35") (pin "+") (pinfunction "+_+") (pintype "passive"))
      (node (ref "C45") (pin "2") (pinfunction "2_2") (pintype "passive"))
      (node (ref "C53") (pin "1") (pinfunction "1_1") (pintype "passive"))
      (node (ref "C55") (pin "2") (pinfunction "2_2") (pintype "passive"))
      (node (ref "C7") (pin "+") (pinfunction "+_+") (pintype "passive"))
      (node (ref "C9") (pin "1") (pinfunction "1_1") (pintype "passive"))
      (node (ref "D1") (pin "A") (pinfunction "A_A") (pintype "passive"))
      (node (ref "D15") (pin "A") (pinfunction "A_A") (pintype "passive"))
      (node (ref "D7") (pin "A") (pinfunction "A_A") (pintype "passive"))
      (node (ref "IC1") (pin "7") (pinfunction "V+_7") (pintype "power_in"))
      (node (ref "IC2") (pin "7") (pinfunction "V+_7") (pintype "power_in"))
      (node (ref "IC3") (pin "7") (pinfunction "V+_7") (pintype "power_in"))
      (node (ref "IC4") (pin "7") (pinfunction "V+_7") (pintype "power_in"))
      (node (ref "IC6") (pin "7") (pinfunction "V+_7") (pintype "power_in"))
      (node (ref "LED1") (pin "A") (pinfunction "A_A") (pintype "passive"))
      (node (ref "LED3") (pin "A") (pinfunction "A_A") (pintype "passive"))
      (node (ref "LED5") (pin "A") (pinfunction "A_A") (pintype "passive"))
      (node (ref "LED7") (pin "A") (pinfunction "A_A") (pintype "passive"))
      (node (ref "Q13") (pin "C") (pinfunction "C_C") (pintype "passive"))
      (node (ref "Q15") (pin "C") (pinfunction "C_C") (pintype "passive"))
      (node (ref "Q17") (pin "C") (pinfunction "C_C") (pintype "passive"))
      (node (ref "Q21") (pin "C") (pinfunction "C_C") (pintype "passive"))
      (node (ref "Q23") (pin "C") (pinfunction "C_C") (pintype "passive"))
      (node (ref "Q46") (pin "C") (pinfunction "C_C") (pintype "passive"))
      (node (ref "Q48") (pin "C") (pinfunction "C_C") (pintype "passive"))
      (node (ref "Q50") (pin "C") (pinfunction "C_C") (pintype "passive"))
      (node (ref "Q73") (pin "C") (pinfunction "C_C") (pintype "passive"))
      (node (ref "Q75") (pin "C") (pinfunction "C_C") (pintype "passive"))
      (node (ref "Q77") (pin "C") (pinfunction "C_C") (pintype "passive"))
      (node (ref "Q89") (pin "E") (pinfunction "E_E") (pintype "passive"))
      (node (ref "Q9") (pin "C") (pinfunction "C_C") (pintype "passive"))
      (node (ref "Q91") (pin "D") (pinfunction "D_D") (pintype "passive"))
      (node (ref "R1") (pin "3") (pinfunction "E_3") (pintype "passive"))
      (node (ref "R103") (pin "2") (pinfunction "2_2") (pintype "passive"))
      (node (ref "R12") (pin "2") (pinfunction "2_2") (pintype "passive"))
      (node (ref "R127") (pin "2") (pinfunction "2_2") (pintype "passive"))
      (node (ref "R131") (pin "2") (pinfunction "2_2") (pintype "passive"))
      (node (ref "R18") (pin "2") (pinfunction "2_2") (pintype "passive"))
      (node (ref "R23") (pin "2") (pinfunction "2_2") (pintype "passive"))
      (node (ref "R38") (pin "2") (pinfunction "2_2") (pintype "passive"))
      (node (ref "R5") (pin "2") (pinfunction "2_2") (pintype "passive"))
      (node (ref "R54") (pin "2") (pinfunction "2_2") (pintype "passive"))
      (node (ref "R58") (pin "2") (pinfunction "2_2") (pintype "passive"))
      (node (ref "R62") (pin "2") (pinfunction "2_2") (pintype "passive"))
      (node (ref "R67") (pin "2") (pinfunction "2_2") (pintype "passive"))
      (node (ref "R71") (pin "2") (pinfunction "2_2") (pintype "passive"))
      (node (ref "R86") (pin "2") (pinfunction "2_2") (pintype "passive"))
      (node (ref "R90") (pin "2") (pinfunction "2_2") (pintype "passive"))
      (node (ref "R94") (pin "2") (pinfunction "2_2") (pintype "passive"))
      (node (ref "R99") (pin "2") (pinfunction "2_2") (pintype "passive"))
    )
    (net (code "203") (name "V-") (class "Default")
      (node (ref "C10") (pin "2") (pinfunction "2_2") (pintype "passive"))
      (node (ref "C12") (pin "2") (pinfunction "2_2") (pintype "passive"))
      (node (ref "C15") (pin "1") (pinfunction "1_1") (pintype "passive"))
      (node (ref "C2") (pin "-") (pinfunction "-_-") (pintype "passive"))
      (node (ref "C24") (pin "2") (pinfunction "2_2") (pintype "passive"))
      (node (ref "C26") (pin "-") (pinfunction "-_-") (pintype "passive"))
      (node (ref "C34") (pin "2") (pinfunction "2_2") (pintype "passive"))
      (node (ref "C36") (pin "-") (pinfunction "-_-") (pintype "passive"))
      (node (ref "C4") (pin "1") (pinfunction "1_1") (pintype "passive"))
      (node (ref "C46") (pin "1") (pinfunction "1_1") (pintype "passive"))
      (node (ref "C54") (pin "2") (pinfunction "2_2") (pintype "passive"))
      (node (ref "C56") (pin "1") (pinfunction "1_1") (pintype "passive"))
      (node (ref "C6") (pin "-") (pinfunction "-_-") (pintype "passive"))
      (node (ref "D10") (pin "C") (pinfunction "C_C") (pintype "passive"))
      (node (ref "D16") (pin "C") (pinfunction "C_C") (pintype "passive"))
      (node (ref "D4") (pin "C") (pinfunction "C_C") (pintype "passive"))
      (node (ref "IC1") (pin "4") (pinfunction "V-_4") (pintype "power_in"))
      (node (ref "IC2") (pin "4") (pinfunction "V-_4") (pintype "power_in"))
      (node (ref "IC3") (pin "4") (pinfunction "V-_4") (pintype "power_in"))
      (node (ref "IC4") (pin "4") (pinfunction "V-_4") (pintype "power_in"))
      (node (ref "IC5") (pin "4") (pinfunction "V-_4") (pintype "power_in"))
      (node (ref "LED2") (pin "C") (pinfunction "C_C") (pintype "passive"))
      (node (ref "LED4") (pin "C") (pinfunction "C_C") (pintype "passive"))
      (node (ref "LED6") (pin "C") (pinfunction "C_C") (pintype "passive"))
      (node (ref "LED8") (pin "C") (pinfunction "C_C") (pintype "passive"))
      (node (ref "Q10") (pin "C") (pinfunction "C_C") (pintype "passive"))
      (node (ref "Q14") (pin "C") (pinfunction "C_C") (pintype "passive"))
      (node (ref "Q16") (pin "C") (pinfunction "C_C") (pintype "passive"))
      (node (ref "Q18") (pin "C") (pinfunction "C_C") (pintype "passive"))
      (node (ref "Q22") (pin "C") (pinfunction "C_C") (pintype "passive"))
      (node (ref "Q24") (pin "C") (pinfunction "C_C") (pintype "passive"))
      (node (ref "Q47") (pin "C") (pinfunction "C_C") (pintype "passive"))
      (node (ref "Q49") (pin "C") (pinfunction "C_C") (pintype "passive"))
      (node (ref "Q51") (pin "C") (pinfunction "C_C") (pintype "passive"))
      (node (ref "Q74") (pin "C") (pinfunction "C_C") (pintype "passive"))
      (node (ref "Q76") (pin "C") (pinfunction "C_C") (pintype "passive"))
      (node (ref "Q78") (pin "C") (pinfunction "C_C") (pintype "passive"))
      (node (ref "Q90") (pin "E") (pinfunction "E_E") (pintype "passive"))
      (node (ref "Q92") (pin "G") (pinfunction "G_G") (pintype "passive"))
      (node (ref "R1") (pin "1") (pinfunction "A_1") (pintype "passive"))
      (node (ref "R102") (pin "1") (pinfunction "1_1") (pintype "passive"))
      (node (ref "R104") (pin "1") (pinfunction "1_1") (pintype "passive"))
      (node (ref "R126") (pin "1") (pinfunction "1_1") (pintype "passive"))
      (node (ref "R13") (pin "1") (pinfunction "1_1") (pintype "passive"))
      (node (ref "R130") (pin "1") (pinfunction "1_1") (pintype "passive"))
      (node (ref "R132") (pin "1") (pinfunction "1_1") (pintype "passive"))
      (node (ref "R19") (pin "1") (pinfunction "1_1") (pintype "passive"))
      (node (ref "R26") (pin "1") (pinfunction "1_1") (pintype "passive"))
      (node (ref "R41") (pin "1") (pinfunction "1_1") (pintype "passive"))
      (node (ref "R57") (pin "1") (pinfunction "1_1") (pintype "passive"))
      (node (ref "R61") (pin "1") (pinfunction "1_1") (pintype "passive"))
      (node (ref "R64") (pin "1") (pinfunction "1_1") (pintype "passive"))
      (node (ref "R7") (pin "1") (pinfunction "1_1") (pintype "passive"))
      (node (ref "R70") (pin "1") (pinfunction "1_1") (pintype "passive"))
      (node (ref "R72") (pin "1") (pinfunction "1_1") (pintype "passive"))
      (node (ref "R89") (pin "1") (pinfunction "1_1") (pintype "passive"))
      (node (ref "R93") (pin "1") (pinfunction "1_1") (pintype "passive"))
      (node (ref "R96") (pin "1") (pinfunction "1_1") (pintype "passive"))
    )
    (net (code "204") (name "unconnected-(IC1-TRIM1-Pad1)") (class "Default")
      (node (ref "IC1") (pin "1") (pinfunction "TRIM1_1") (pintype "passive"))
    )
    (net (code "205") (name "unconnected-(IC1-TRIM2-Pad5)") (class "Default")
      (node (ref "IC1") (pin "5") (pinfunction "TRIM2_5") (pintype "passive"))
    )
    (net (code "206") (name "unconnected-(IC2-TRIM1-Pad1)") (class "Default")
      (node (ref "IC2") (pin "1") (pinfunction "TRIM1_1") (pintype "passive"))
    )
    (net (code "207") (name "unconnected-(IC2-TRIM2-Pad5)") (class "Default")
      (node (ref "IC2") (pin "5") (pinfunction "TRIM2_5") (pintype "passive"))
    )
    (net (code "208") (name "unconnected-(IC3-CMP1-Pad1)") (class "Default")
      (node (ref "IC3") (pin "1") (pinfunction "CMP1_1") (pintype "passive"))
    )
    (net (code "209") (name "unconnected-(IC3-CMP2-Pad8)") (class "Default")
      (node (ref "IC3") (pin "8") (pinfunction "CMP2_8") (pintype "passive"))
    )
    (net (code "210") (name "unconnected-(IC4-CMP1-Pad1)") (class "Default")
      (node (ref "IC4") (pin "1") (pinfunction "CMP1_1") (pintype "passive"))
    )
    (net (code "211") (name "unconnected-(IC4-CMP2-Pad8)") (class "Default")
      (node (ref "IC4") (pin "8") (pinfunction "CMP2_8") (pintype "passive"))
    )
    (net (code "212") (name "unconnected-(IC5-CMP1-Pad1)") (class "Default")
      (node (ref "IC5") (pin "1") (pinfunction "CMP1_1") (pintype "passive"))
    )
    (net (code "213") (name "unconnected-(IC5-CMP2-Pad8)") (class "Default")
      (node (ref "IC5") (pin "8") (pinfunction "CMP2_8") (pintype "passive"))
    )
    (net (code "214") (name "unconnected-(IC6-CMP1-Pad1)") (class "Default")
      (node (ref "IC6") (pin "1") (pinfunction "CMP1_1") (pintype "passive"))
    )
    (net (code "215") (name "unconnected-(IC6-CMP2-Pad8)") (class "Default")
      (node (ref "IC6") (pin "8") (pinfunction "CMP2_8") (pintype "passive"))
    )
  )
)
